# TeensySensor.net
KiCad netlist of a schematic drawn in EasyEDA Pro
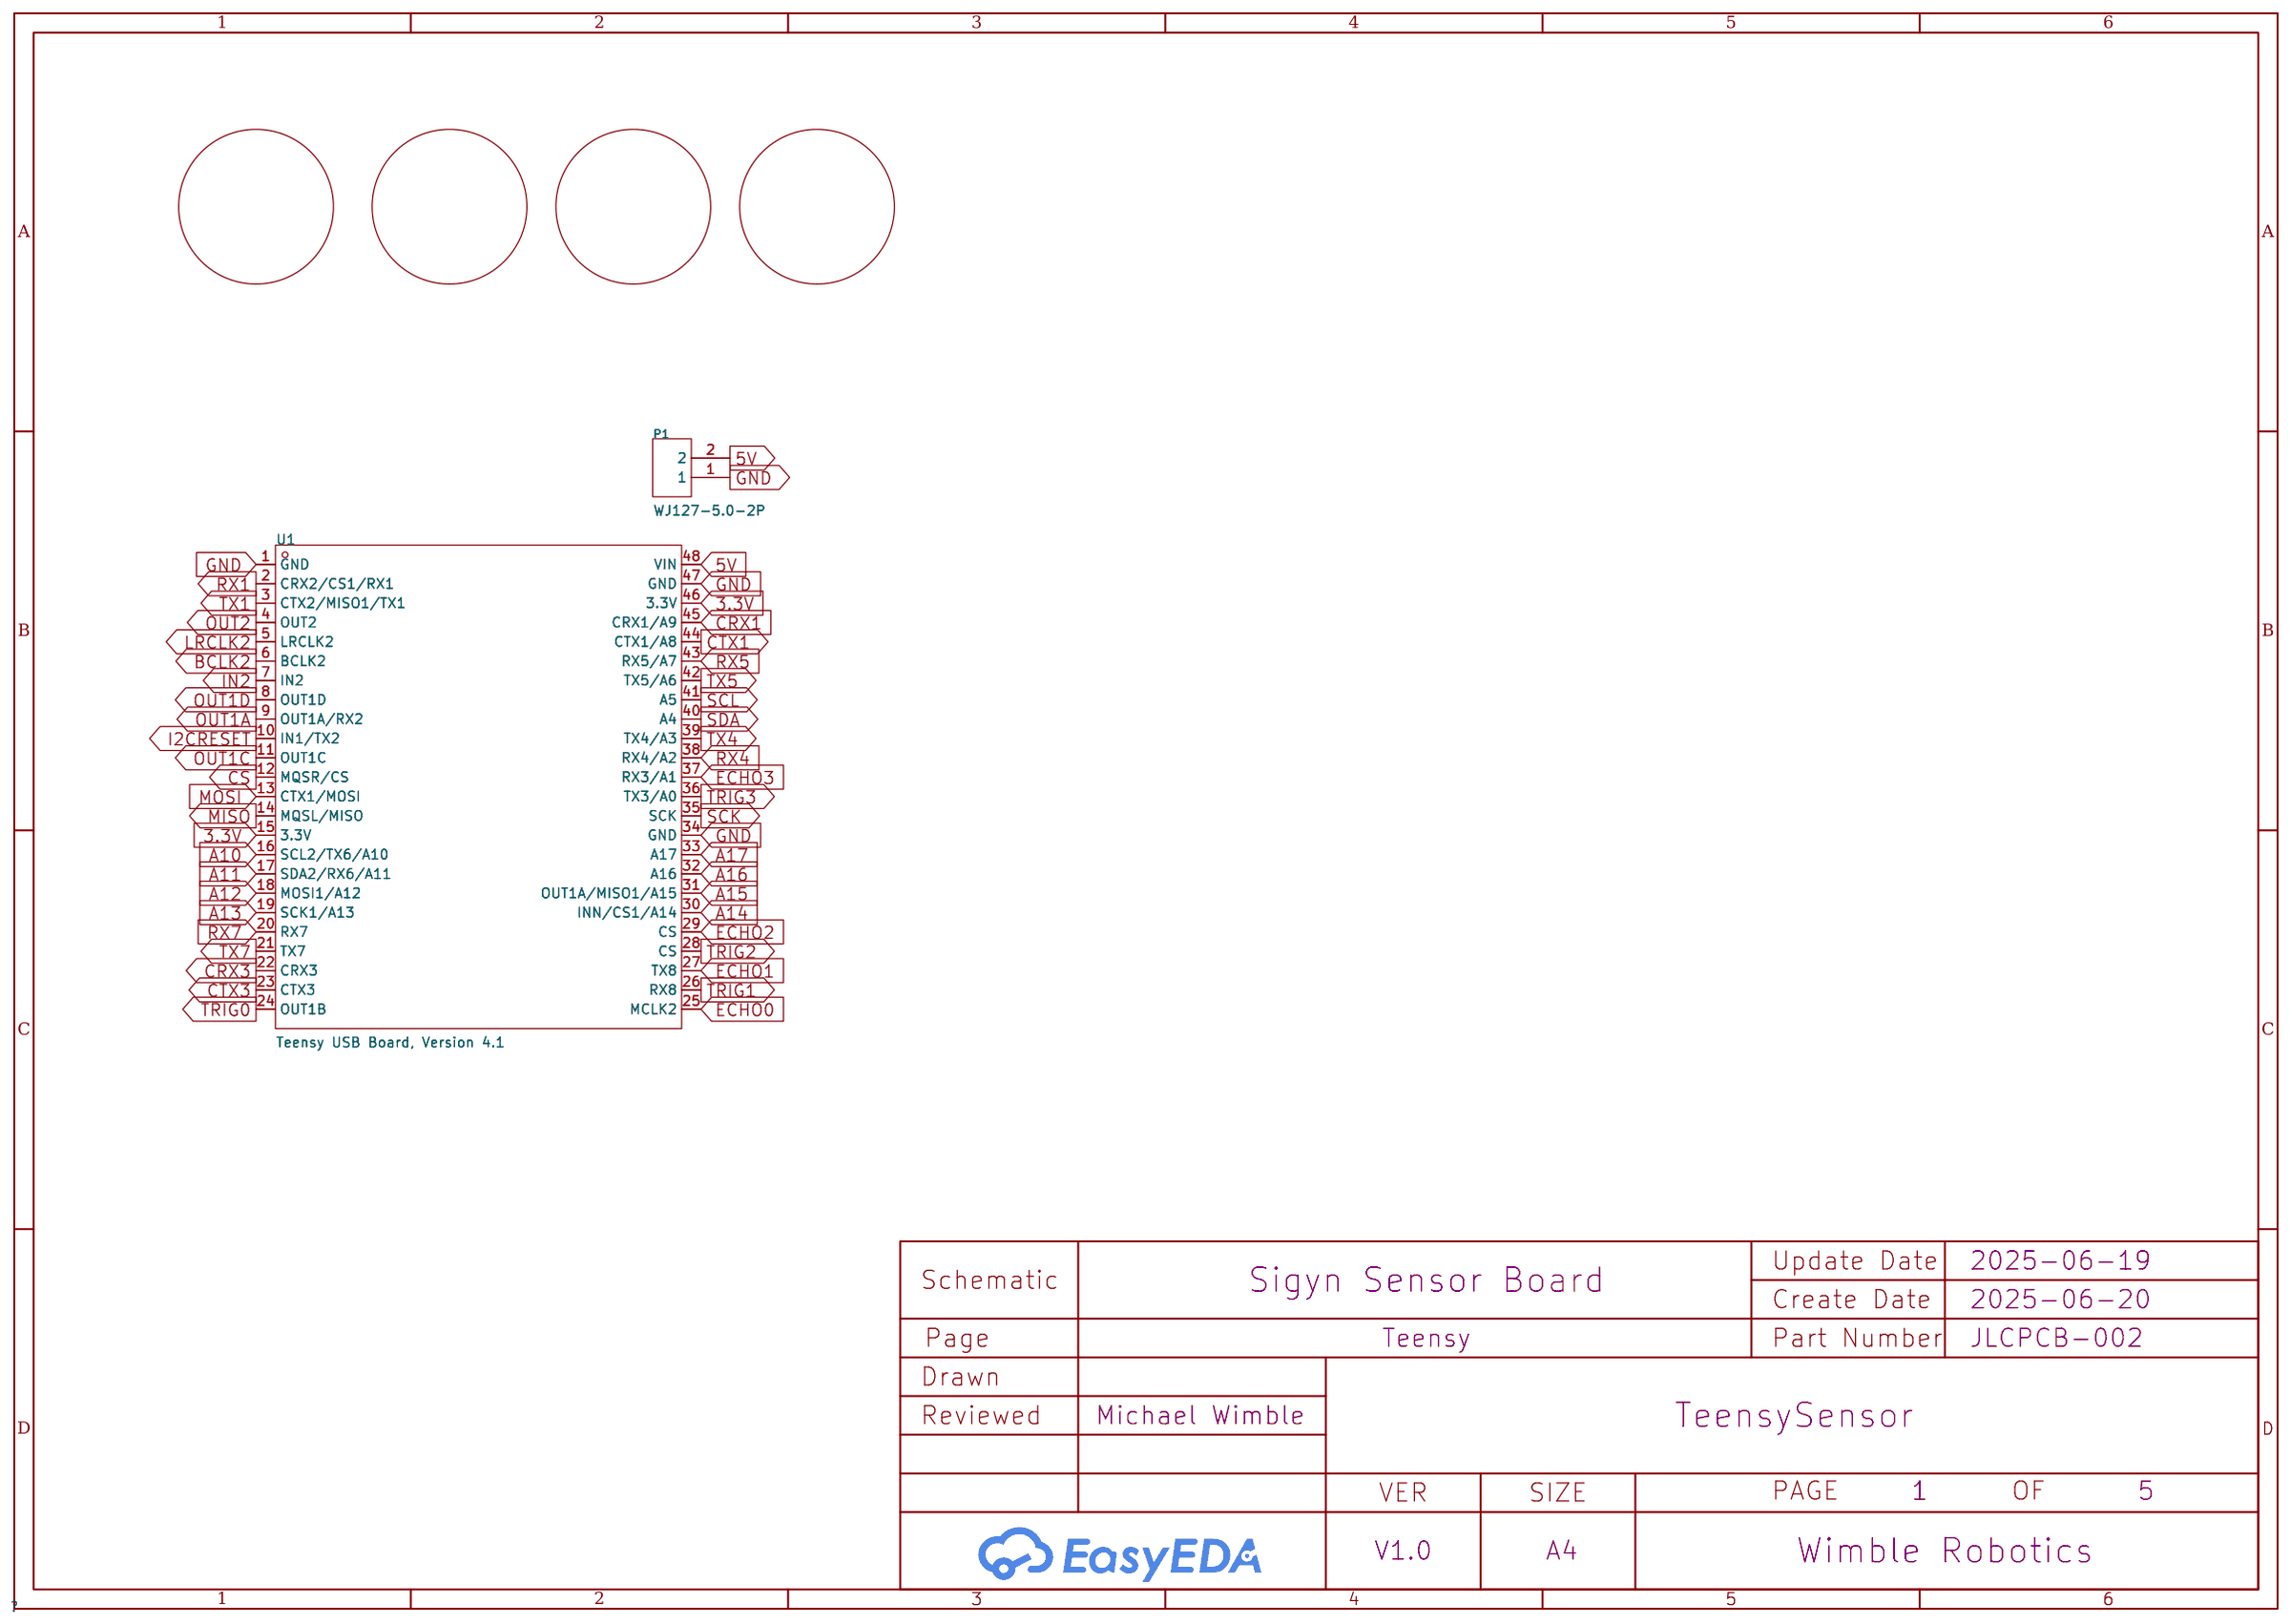
[diagram p0: Teensy]
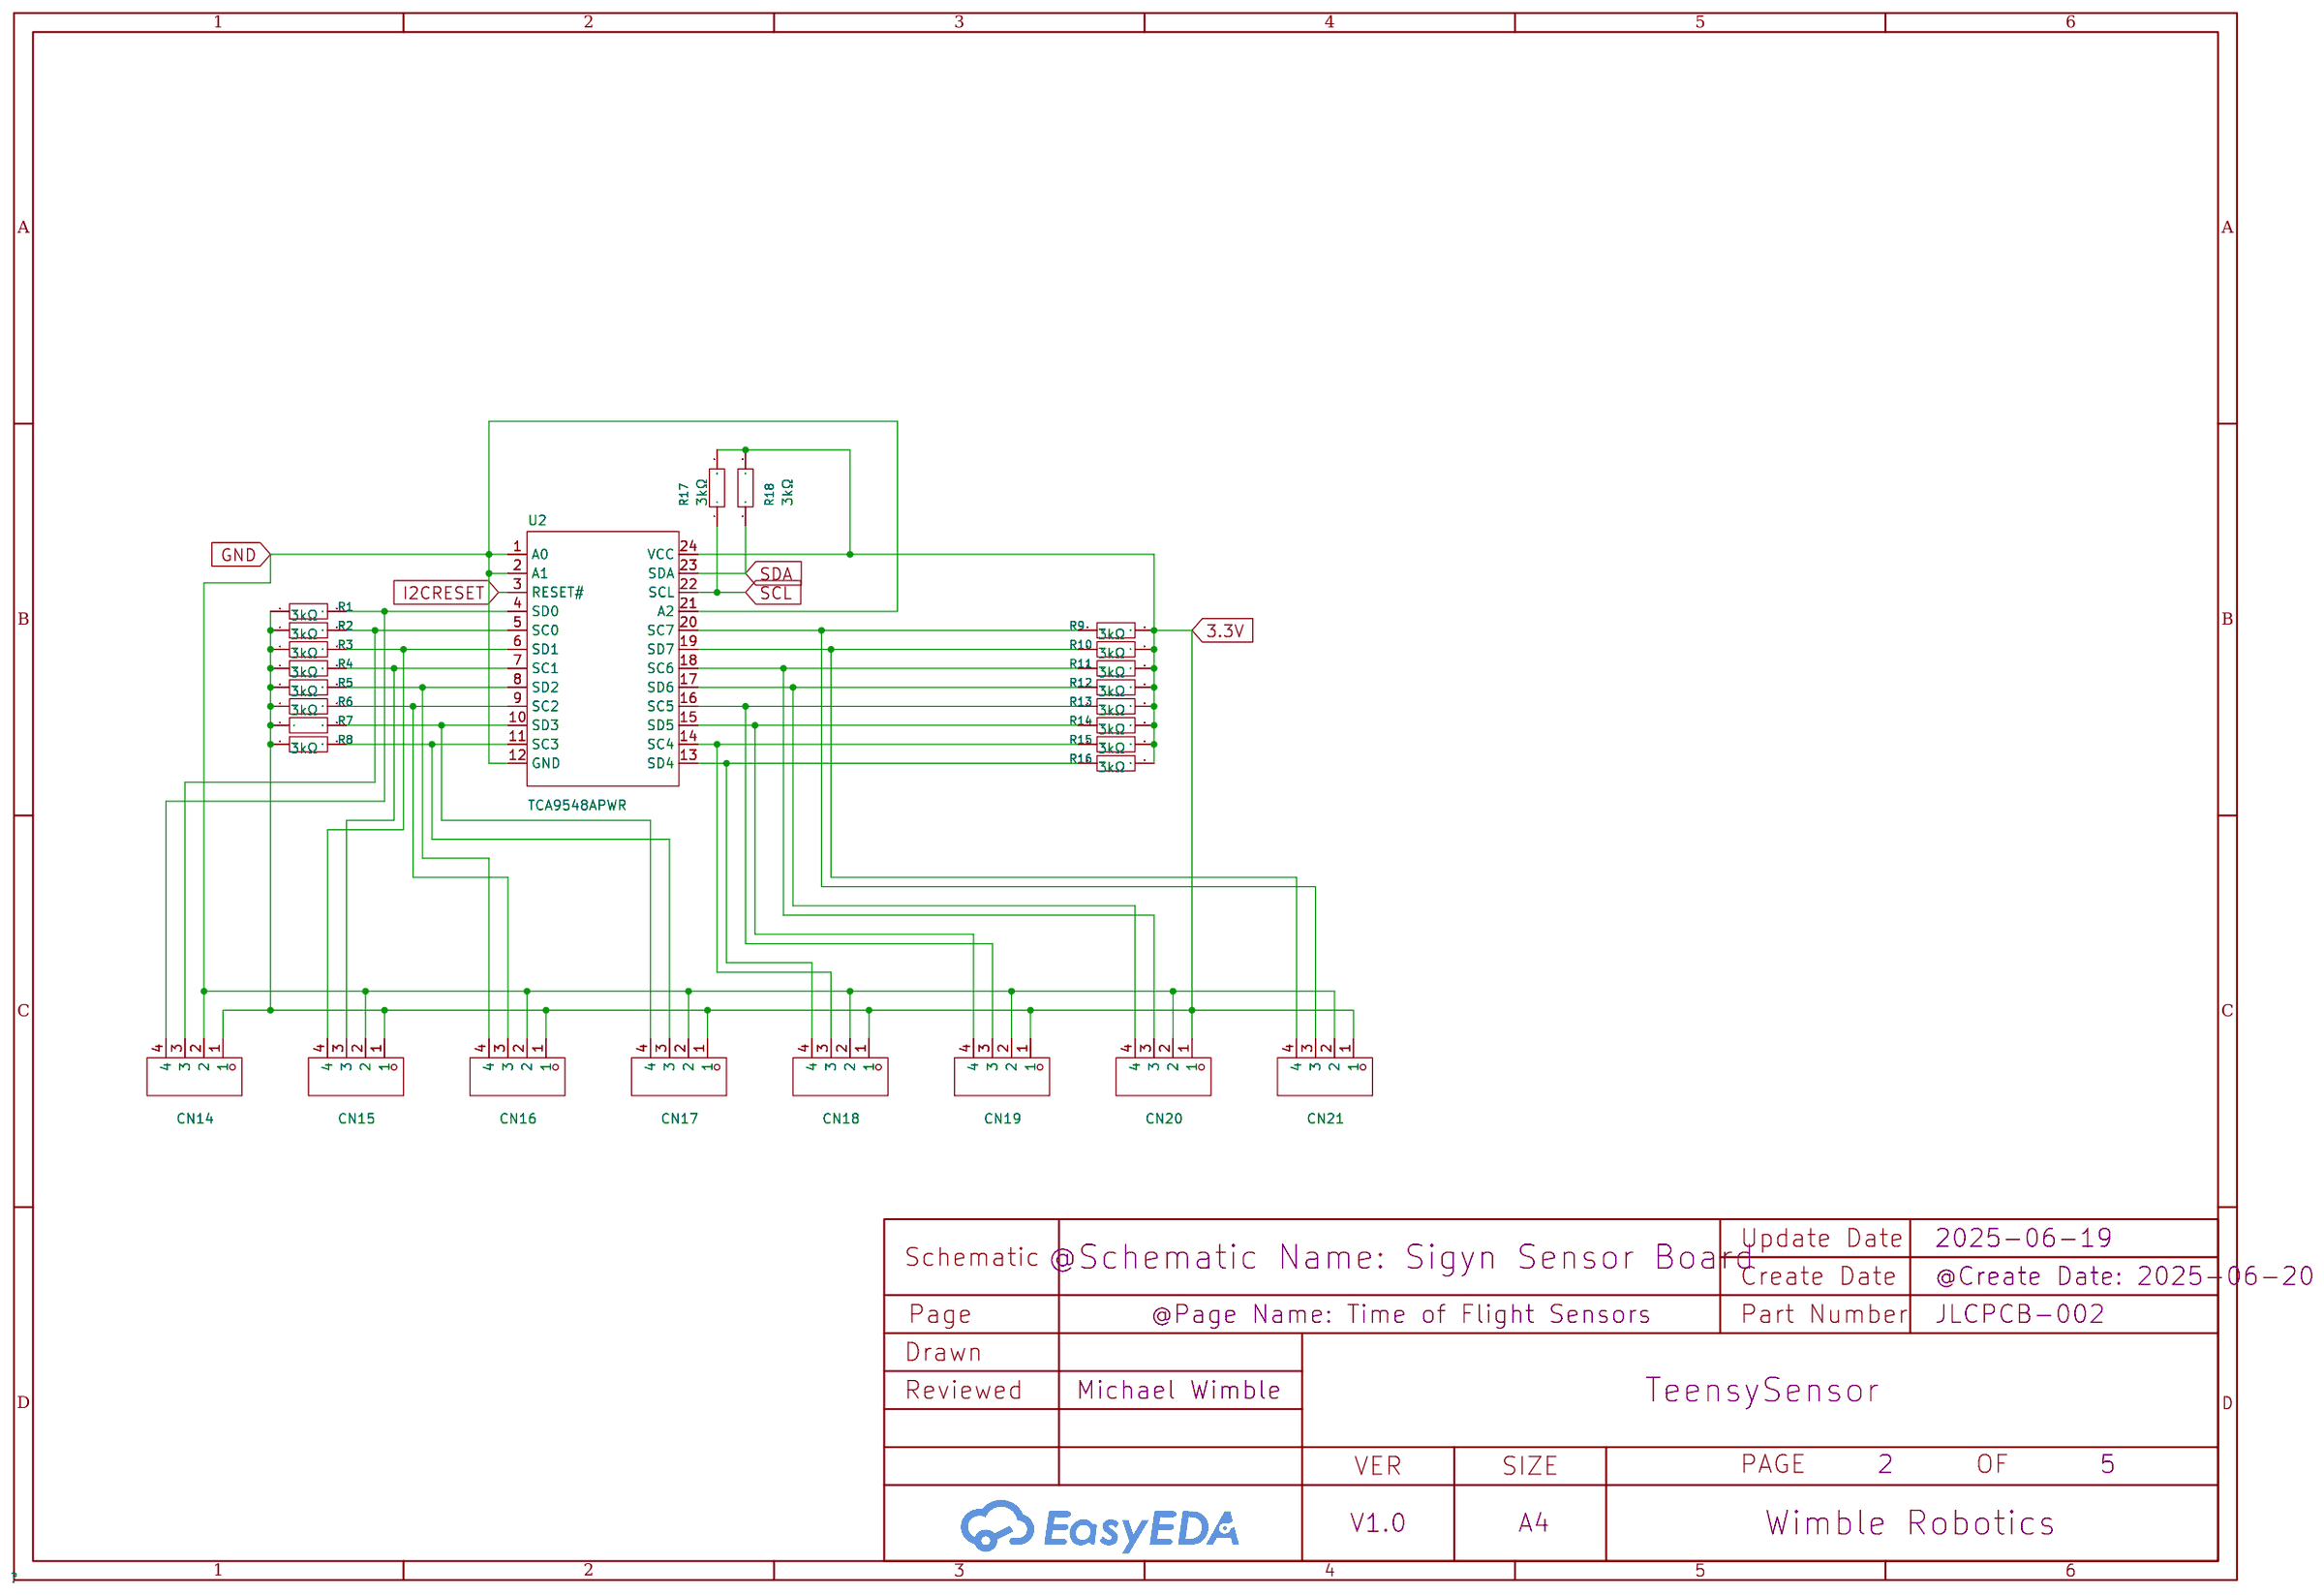
[diagram p1: Time of Flight Sensors]
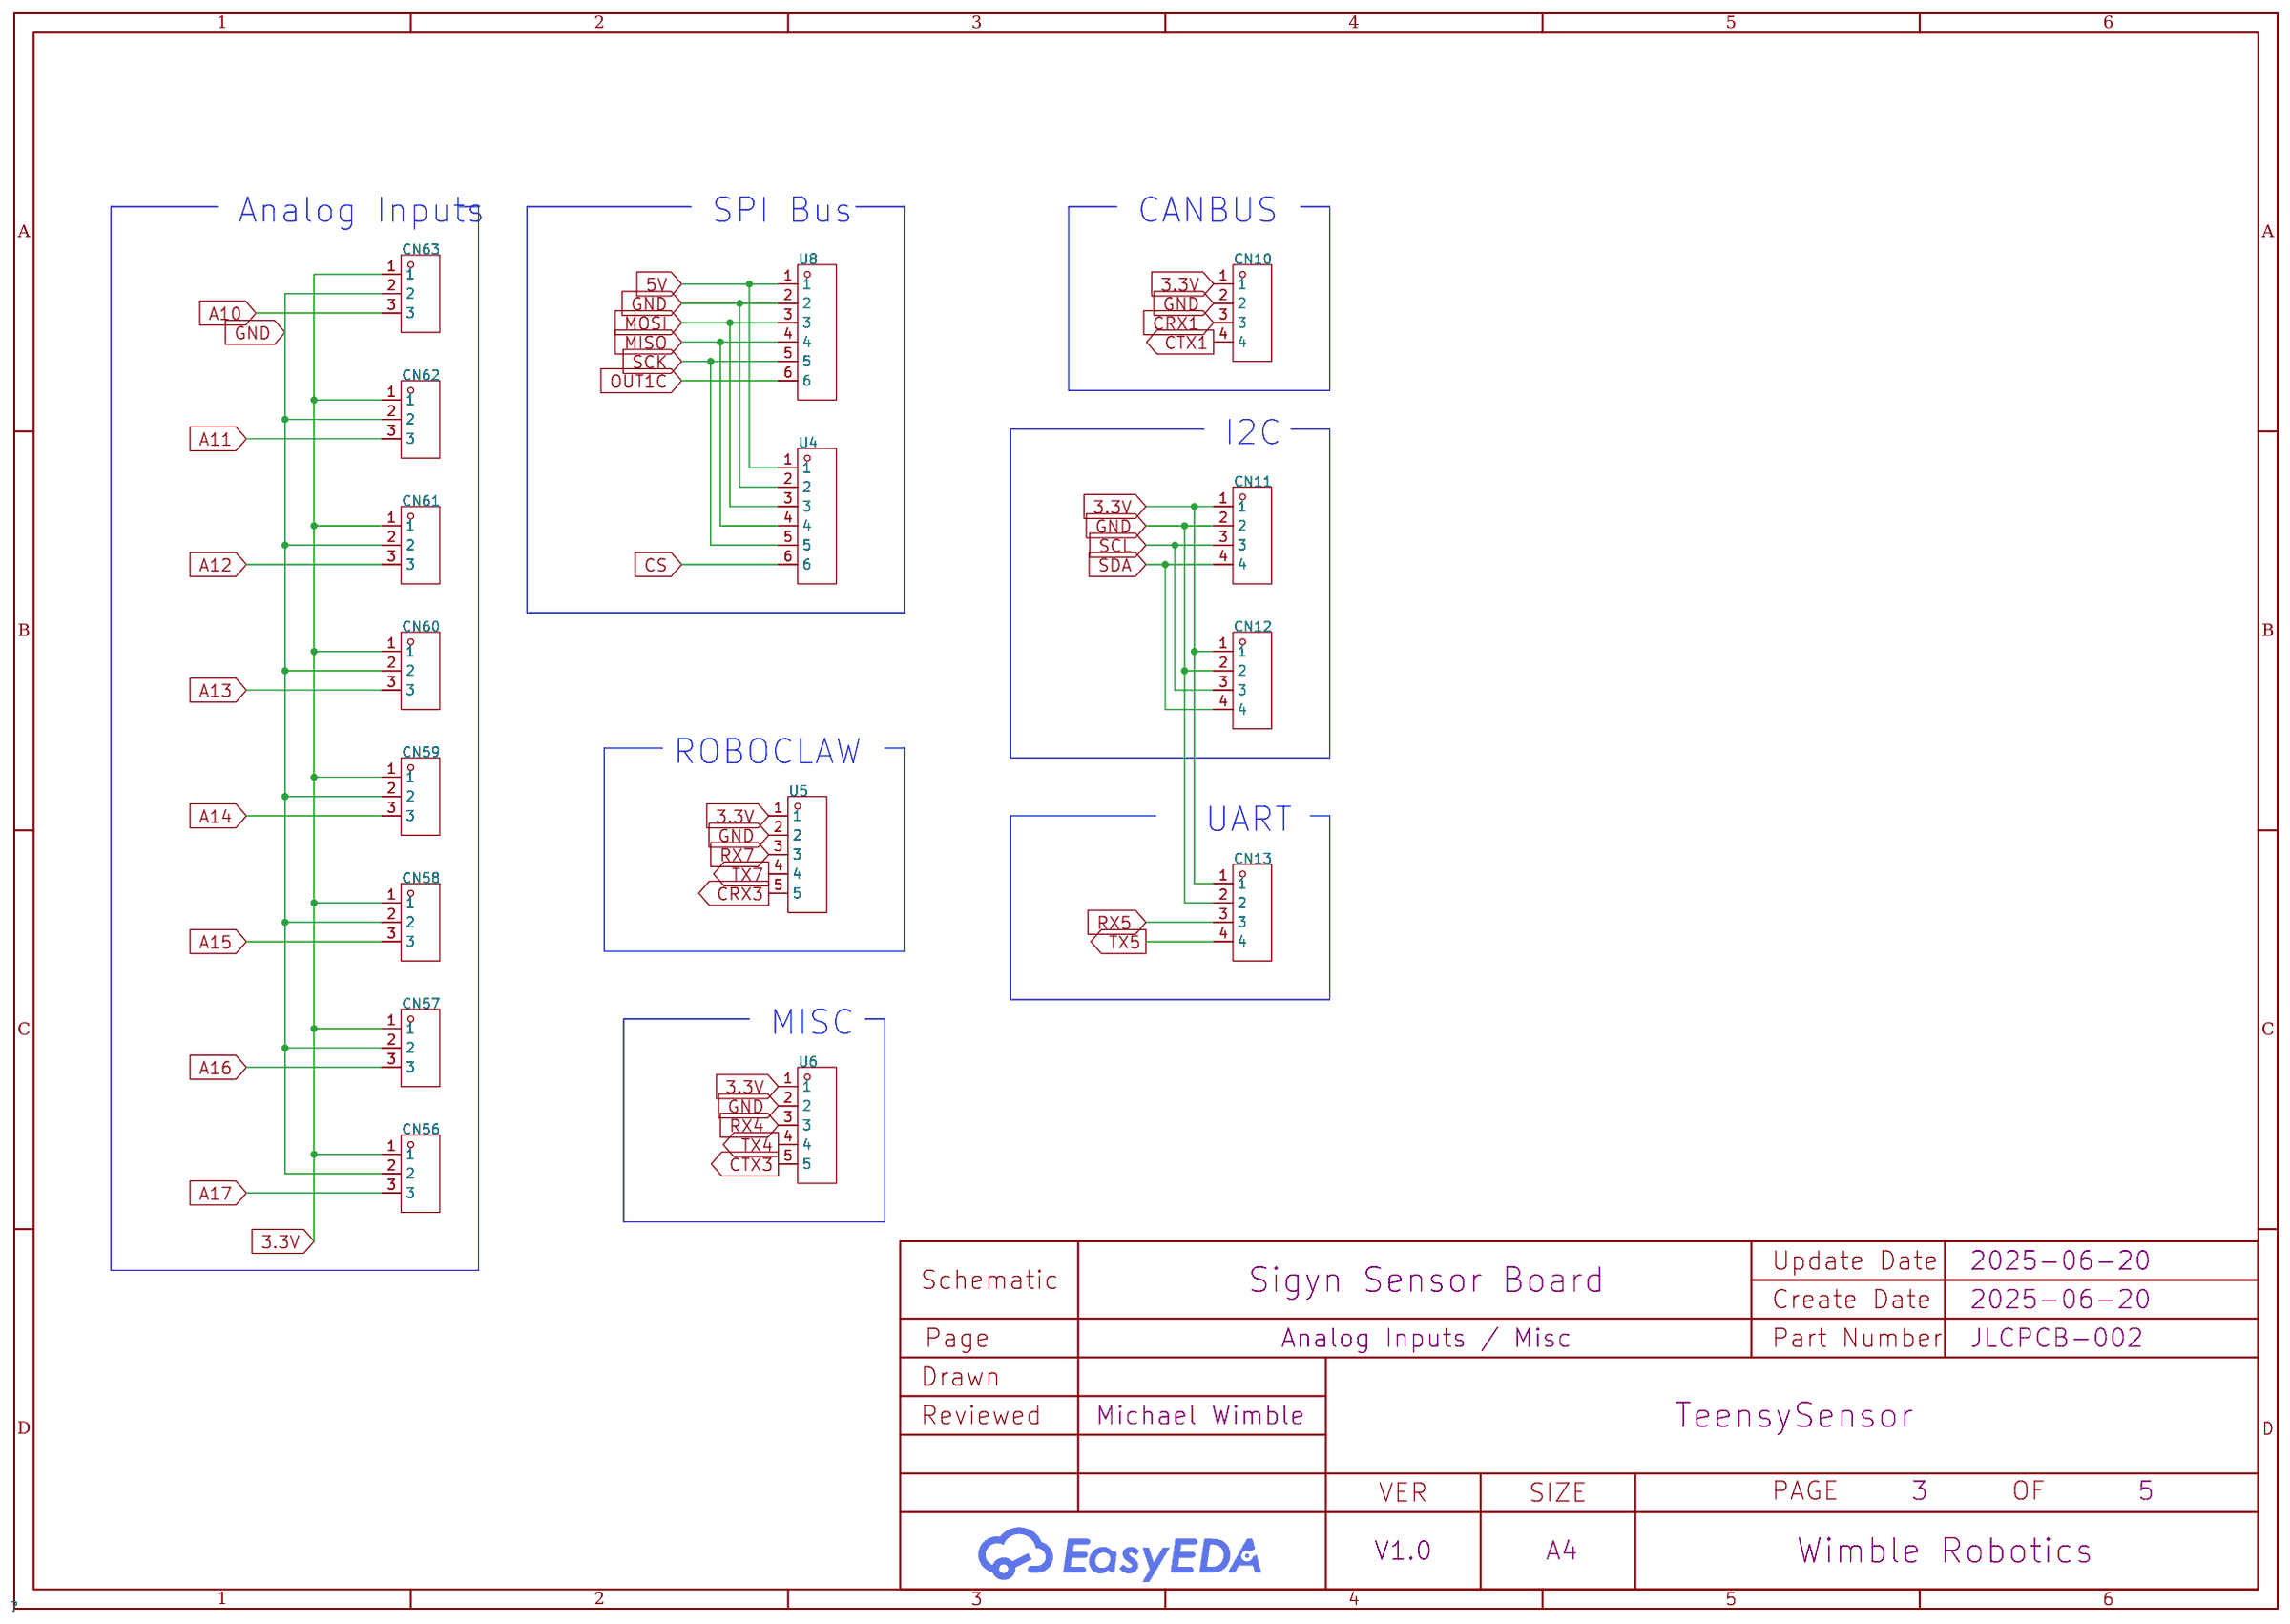
[diagram p2: Analog Inputs / Misc]
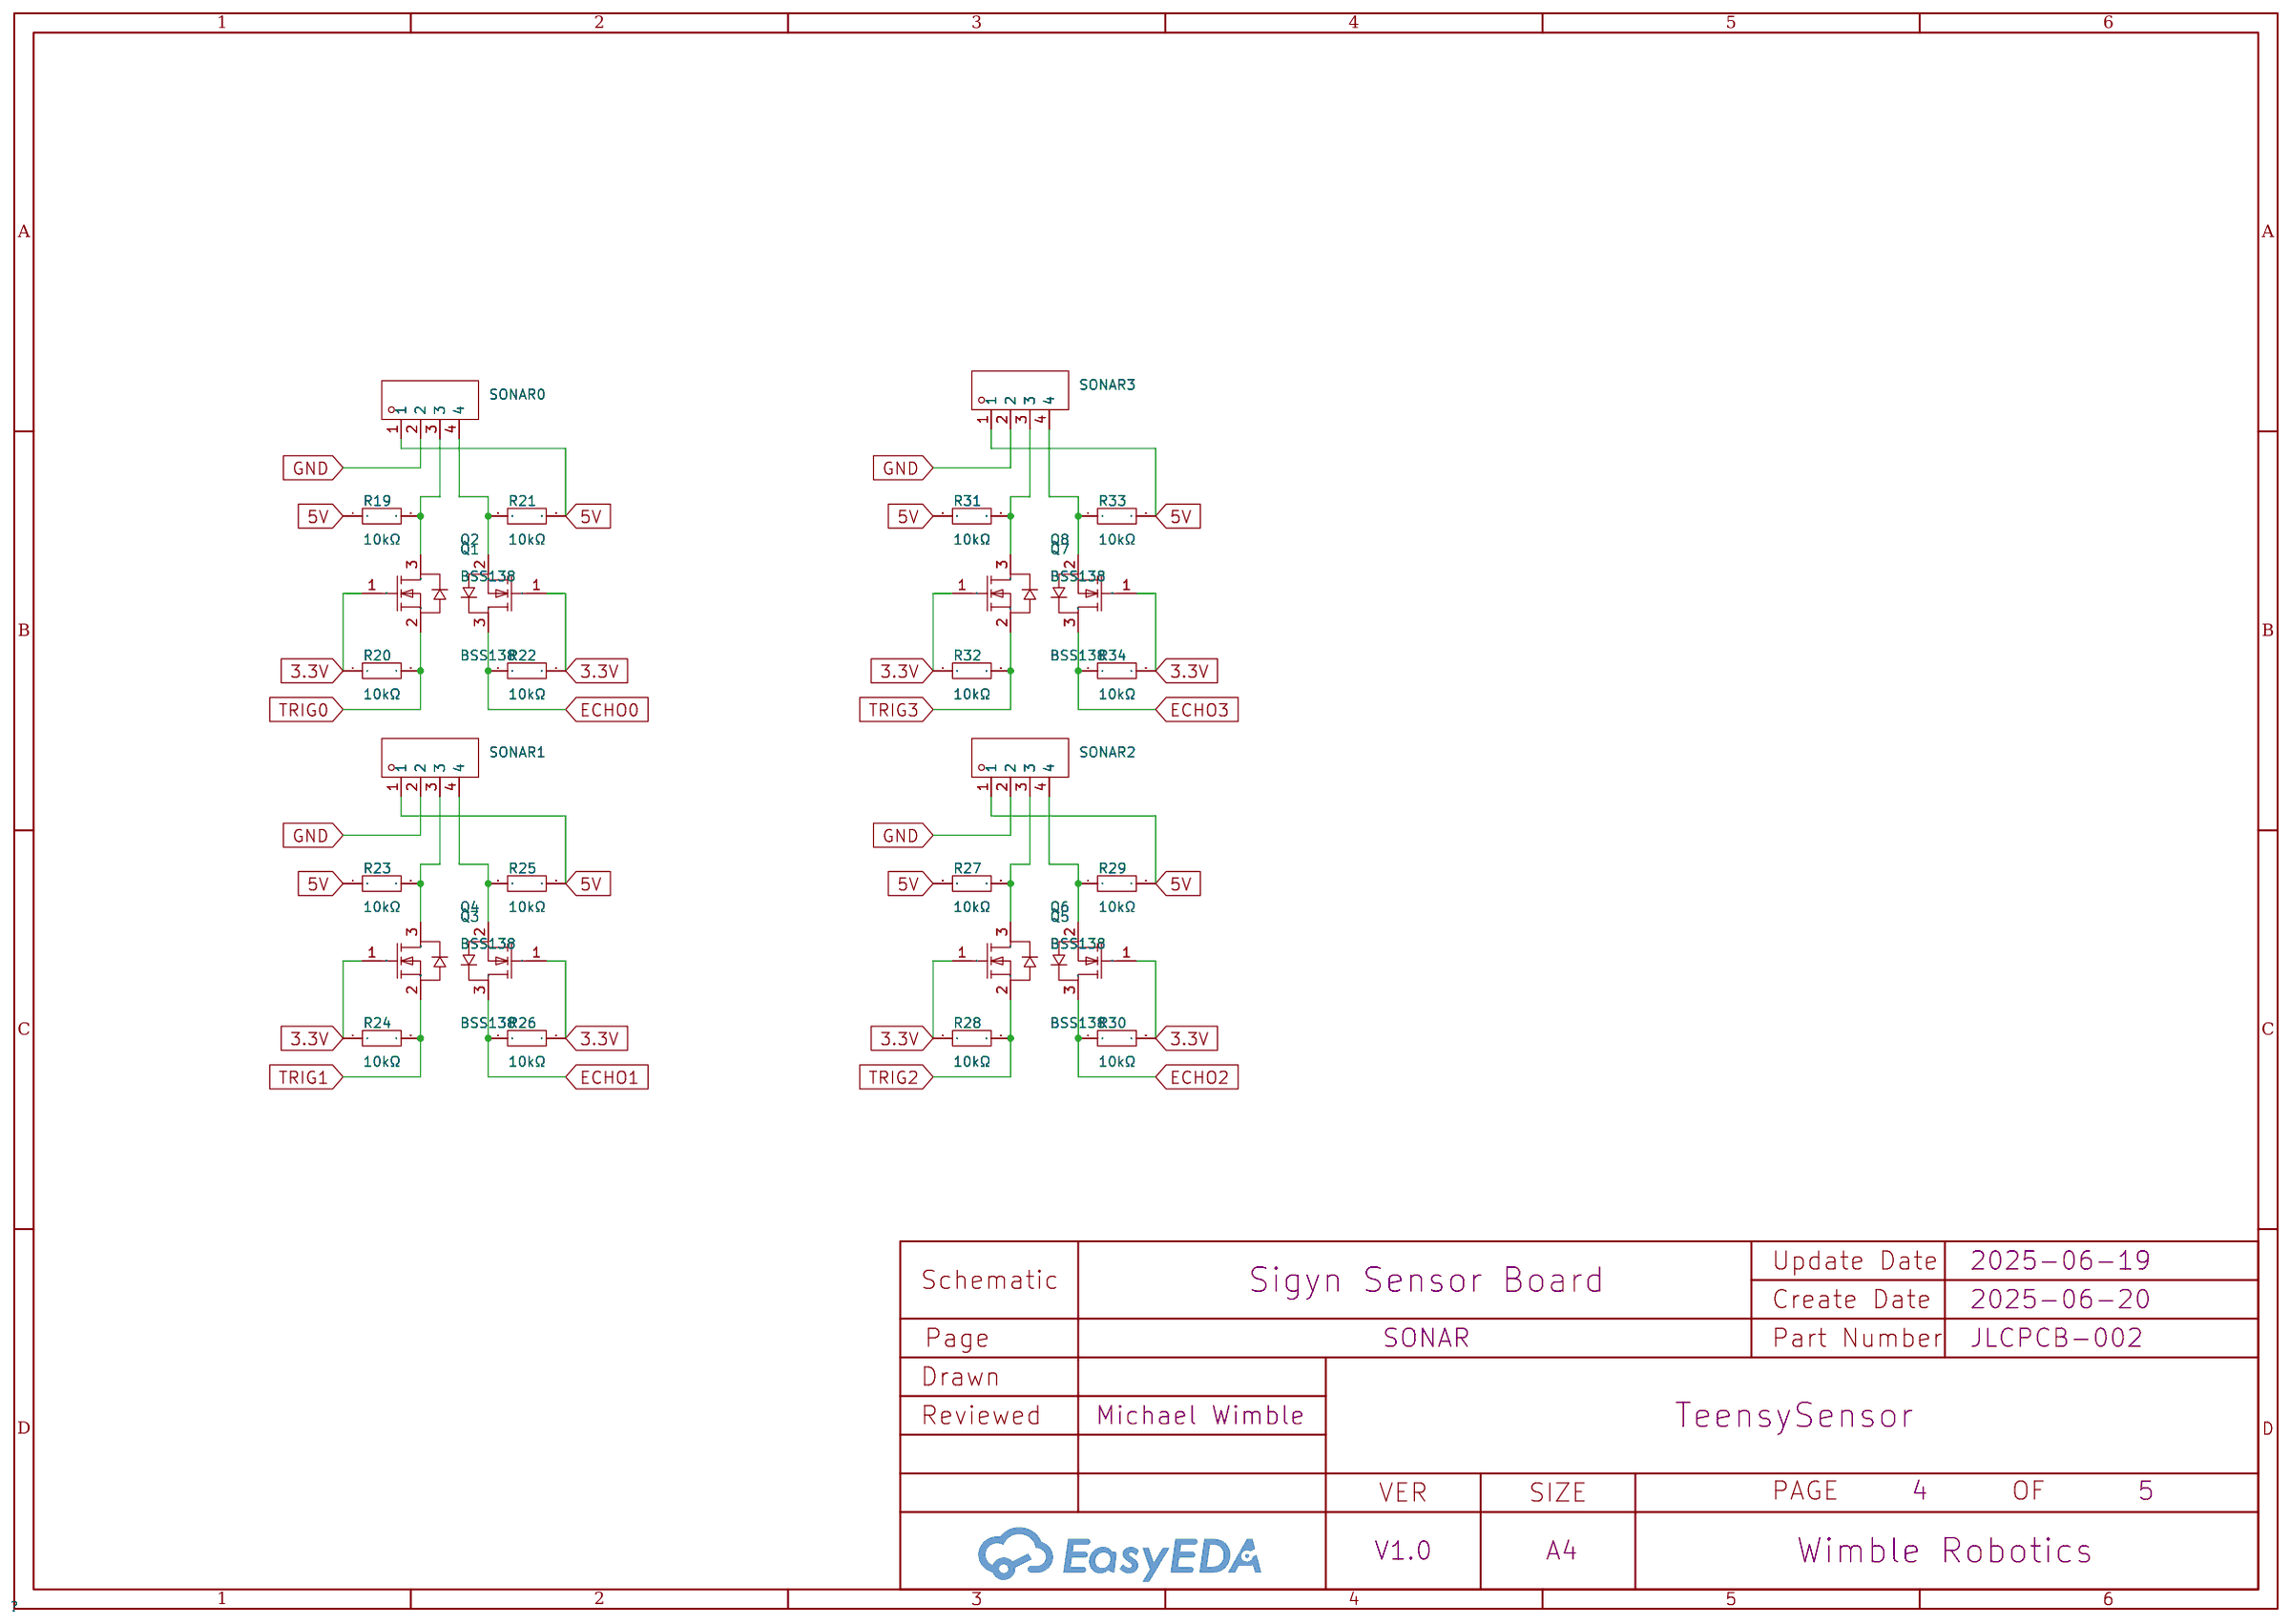
[diagram p3: SONAR]
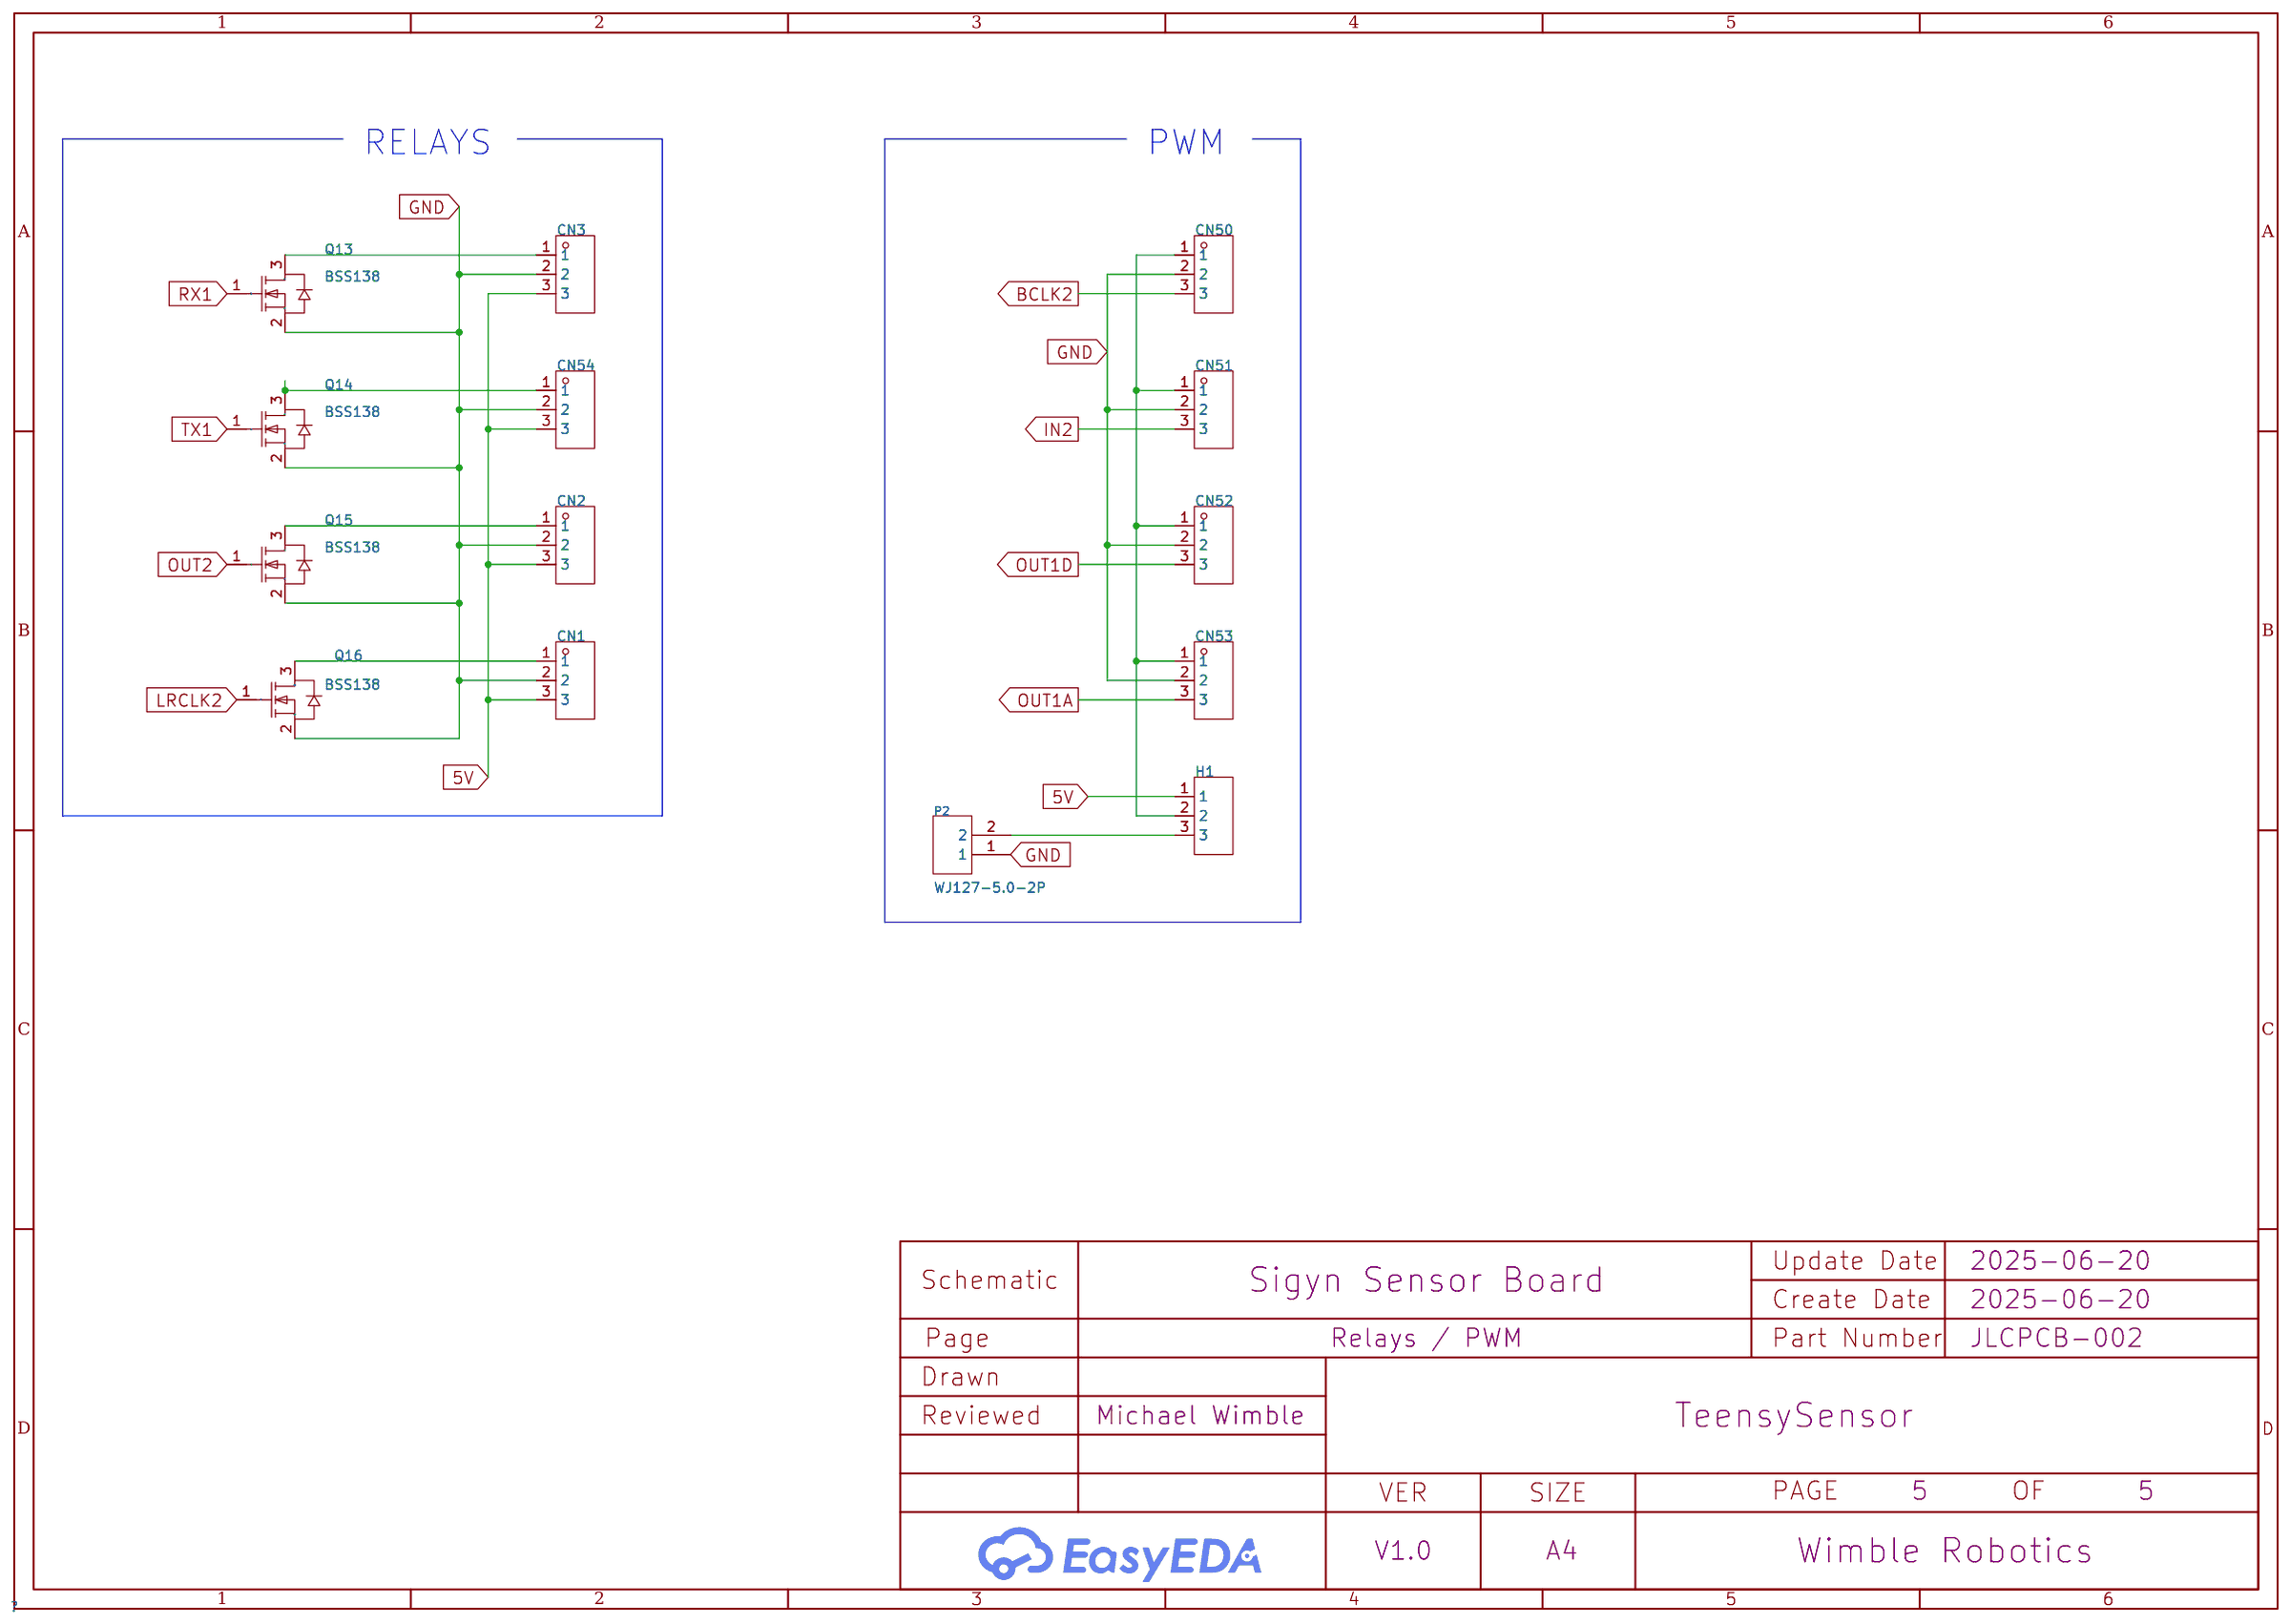
[diagram p4: Relays / PWM]

(export (version "E")
  (design (tool "Eeschema 10.0.6"))
  (components
    (comp (ref "P1")
      (value "WJ127-5.0-2P")
      (footprint "easyedapro:CONN-TH_2P-P5.00_CPC3703CTR")
      (fields (field (name "Manufacturer") "KANGNEX(康奈克斯电气)"))
      (libsource (lib "easyedapro") (part "WJ127-5.0-2P"))
    )
    (comp (ref "U1")
      (value "Teensy USB Board, Version 4.1")
      (footprint "easyedapro:COMM-TH_L61.0-W17.8-P2.54")
      (libsource (lib "easyedapro") (part "TEENSY USB BOARD, VERSION 4.1"))
    )
    (comp (ref "U12")
      (value "~")
      (footprint "easyedapro:3.5mm_Hole")
      (description "Mounting hole")
      (libsource (lib "easyedapro") (part "3.5MMHole"))
    )
    (comp (ref "U13")
      (value "~")
      (footprint "easyedapro:3.5mm_Hole")
      (description "Mounting hole")
      (libsource (lib "easyedapro") (part "3.5MMHole"))
    )
    (comp (ref "U14")
      (value "~")
      (footprint "easyedapro:3.5mm_Hole")
      (description "Mounting hole")
      (libsource (lib "easyedapro") (part "3.5MMHole"))
    )
    (comp (ref "U15")
      (value "~")
      (footprint "easyedapro:3.5mm_Hole")
      (description "Mounting hole")
      (libsource (lib "easyedapro") (part "3.5MMHole"))
    )
    (comp (ref "CN14")
      (value "ZX-XH2.54-4PZZ")
      (footprint "easyedapro:CONN-TH_4P-P2.50_4PIN")
      (fields (field (name "Manufacturer") "Megastar(兆星)"))
      (libsource (lib "easyedapro") (part "ZX-XH2.54-4PZZ"))
    )
    (comp (ref "CN15")
      (value "ZX-XH2.54-4PZZ")
      (footprint "easyedapro:CONN-TH_4P-P2.50_4PIN")
      (fields (field (name "Manufacturer") "Megastar(兆星)"))
      (libsource (lib "easyedapro") (part "ZX-XH2.54-4PZZ"))
    )
    (comp (ref "CN16")
      (value "ZX-XH2.54-4PZZ")
      (footprint "easyedapro:CONN-TH_4P-P2.50_4PIN")
      (fields (field (name "Manufacturer") "Megastar(兆星)"))
      (libsource (lib "easyedapro") (part "ZX-XH2.54-4PZZ"))
    )
    (comp (ref "CN17")
      (value "ZX-XH2.54-4PZZ")
      (footprint "easyedapro:CONN-TH_4P-P2.50_4PIN")
      (fields (field (name "Manufacturer") "Megastar(兆星)"))
      (libsource (lib "easyedapro") (part "ZX-XH2.54-4PZZ"))
    )
    (comp (ref "CN18")
      (value "ZX-XH2.54-4PZZ")
      (footprint "easyedapro:CONN-TH_4P-P2.50_4PIN")
      (fields (field (name "Manufacturer") "Megastar(兆星)"))
      (libsource (lib "easyedapro") (part "ZX-XH2.54-4PZZ"))
    )
    (comp (ref "CN19")
      (value "ZX-XH2.54-4PZZ")
      (footprint "easyedapro:CONN-TH_4P-P2.50_4PIN")
      (fields (field (name "Manufacturer") "Megastar(兆星)"))
      (libsource (lib "easyedapro") (part "ZX-XH2.54-4PZZ"))
    )
    (comp (ref "CN20")
      (value "ZX-XH2.54-4PZZ")
      (footprint "easyedapro:CONN-TH_4P-P2.50_4PIN")
      (fields (field (name "Manufacturer") "Megastar(兆星)"))
      (libsource (lib "easyedapro") (part "ZX-XH2.54-4PZZ"))
    )
    (comp (ref "CN21")
      (value "ZX-XH2.54-4PZZ")
      (footprint "easyedapro:CONN-TH_4P-P2.50_4PIN")
      (fields (field (name "Manufacturer") "Megastar(兆星)"))
      (libsource (lib "easyedapro") (part "ZX-XH2.54-4PZZ"))
    )
    (comp (ref "R1")
      (value "3kΩ")
      (footprint "easyedapro:R0603")
      (fields
        (field (name "Manufacturer Part") "0603WAF3001T5E")
        (field (name "Manufacturer") "UNI-ROYAL(厚声)")
      )
      (libsource (lib "easyedapro") (part "0603WAF3001T5E"))
    )
    (comp (ref "R2")
      (value "3kΩ")
      (footprint "easyedapro:R0603")
      (fields
        (field (name "Manufacturer Part") "0603WAF3001T5E")
        (field (name "Manufacturer") "UNI-ROYAL(厚声)")
      )
      (libsource (lib "easyedapro") (part "0603WAF3001T5E"))
    )
    (comp (ref "R3")
      (value "3kΩ")
      (footprint "easyedapro:R0603")
      (fields
        (field (name "Manufacturer Part") "0603WAF3001T5E")
        (field (name "Manufacturer") "UNI-ROYAL(厚声)")
      )
      (libsource (lib "easyedapro") (part "0603WAF3001T5E"))
    )
    (comp (ref "R4")
      (value "3kΩ")
      (footprint "easyedapro:R0603")
      (fields
        (field (name "Manufacturer Part") "0603WAF3001T5E")
        (field (name "Manufacturer") "UNI-ROYAL(厚声)")
      )
      (libsource (lib "easyedapro") (part "0603WAF3001T5E"))
    )
    (comp (ref "R5")
      (value "3kΩ")
      (footprint "easyedapro:R0603")
      (fields
        (field (name "Manufacturer Part") "0603WAF3001T5E")
        (field (name "Manufacturer") "UNI-ROYAL(厚声)")
      )
      (libsource (lib "easyedapro") (part "0603WAF3001T5E"))
    )
    (comp (ref "R6")
      (value "3kΩ")
      (footprint "easyedapro:R0603")
      (fields
        (field (name "Manufacturer Part") "0603WAF3001T5E")
        (field (name "Manufacturer") "UNI-ROYAL(厚声)")
      )
      (libsource (lib "easyedapro") (part "0603WAF3001T5E"))
    )
    (comp (ref "R7")
      (value "3kΩ")
      (footprint "easyedapro:R0603")
      (fields
        (field (name "Manufacturer Part") "0603WAF3001T5E")
        (field (name "Manufacturer") "UNI-ROYAL(厚声)")
      )
      (libsource (lib "easyedapro") (part "0603WAF3001T5E"))
    )
    (comp (ref "R8")
      (value "3kΩ")
      (footprint "easyedapro:R0603")
      (fields
        (field (name "Manufacturer Part") "0603WAF3001T5E")
        (field (name "Manufacturer") "UNI-ROYAL(厚声)")
      )
      (libsource (lib "easyedapro") (part "0603WAF3001T5E"))
    )
    (comp (ref "R9")
      (value "3kΩ")
      (footprint "easyedapro:R0603")
      (fields
        (field (name "Manufacturer Part") "0603WAF3001T5E")
        (field (name "Manufacturer") "UNI-ROYAL(厚声)")
      )
      (libsource (lib "easyedapro") (part "0603WAF3001T5E"))
    )
    (comp (ref "R10")
      (value "3kΩ")
      (footprint "easyedapro:R0603")
      (fields
        (field (name "Manufacturer Part") "0603WAF3001T5E")
        (field (name "Manufacturer") "UNI-ROYAL(厚声)")
      )
      (libsource (lib "easyedapro") (part "0603WAF3001T5E"))
    )
    (comp (ref "R11")
      (value "3kΩ")
      (footprint "easyedapro:R0603")
      (fields
        (field (name "Manufacturer Part") "0603WAF3001T5E")
        (field (name "Manufacturer") "UNI-ROYAL(厚声)")
      )
      (libsource (lib "easyedapro") (part "0603WAF3001T5E"))
    )
    (comp (ref "R12")
      (value "3kΩ")
      (footprint "easyedapro:R0603")
      (fields
        (field (name "Manufacturer Part") "0603WAF3001T5E")
        (field (name "Manufacturer") "UNI-ROYAL(厚声)")
      )
      (libsource (lib "easyedapro") (part "0603WAF3001T5E"))
    )
    (comp (ref "R13")
      (value "3kΩ")
      (footprint "easyedapro:R0603")
      (fields
        (field (name "Manufacturer Part") "0603WAF3001T5E")
        (field (name "Manufacturer") "UNI-ROYAL(厚声)")
      )
      (libsource (lib "easyedapro") (part "0603WAF3001T5E"))
    )
    (comp (ref "R14")
      (value "3kΩ")
      (footprint "easyedapro:R0603")
      (fields
        (field (name "Manufacturer Part") "0603WAF3001T5E")
        (field (name "Manufacturer") "UNI-ROYAL(厚声)")
      )
      (libsource (lib "easyedapro") (part "0603WAF3001T5E"))
    )
    (comp (ref "R15")
      (value "3kΩ")
      (footprint "easyedapro:R0603")
      (fields
        (field (name "Manufacturer Part") "0603WAF3001T5E")
        (field (name "Manufacturer") "UNI-ROYAL(厚声)")
      )
      (libsource (lib "easyedapro") (part "0603WAF3001T5E"))
    )
    (comp (ref "R16")
      (value "3kΩ")
      (footprint "easyedapro:R0603")
      (fields
        (field (name "Manufacturer Part") "0603WAF3001T5E")
        (field (name "Manufacturer") "UNI-ROYAL(厚声)")
      )
      (libsource (lib "easyedapro") (part "0603WAF3001T5E"))
    )
    (comp (ref "R17")
      (value "3kΩ")
      (footprint "easyedapro:R0603")
      (fields
        (field (name "Manufacturer Part") "0603WAF3001T5E")
        (field (name "Manufacturer") "UNI-ROYAL(厚声)")
      )
      (libsource (lib "easyedapro") (part "0603WAF3001T5E"))
    )
    (comp (ref "R18")
      (value "3kΩ")
      (footprint "easyedapro:R0603")
      (fields
        (field (name "Manufacturer Part") "0603WAF3001T5E")
        (field (name "Manufacturer") "UNI-ROYAL(厚声)")
      )
      (libsource (lib "easyedapro") (part "0603WAF3001T5E"))
    )
    (comp (ref "U2")
      (value "TCA9548APWR")
      (footprint "easyedapro:TSSOP-24_L7.8-W4.4-P0.65-LS6.4-BL")
      (fields (field (name "Manufacturer") "TI(德州仪器)"))
      (libsource (lib "easyedapro") (part "TCA9548APWR"))
    )
    (comp (ref "CN10")
      (value "ZX-XH2.54-4PZZ")
      (footprint "easyedapro:CONN-TH_4P-P2.50_4PIN")
      (fields (field (name "Manufacturer") "Megastar(兆星)"))
      (libsource (lib "easyedapro") (part "ZX-XH2.54-4PZZ"))
    )
    (comp (ref "CN11")
      (value "ZX-XH2.54-4PZZ")
      (footprint "easyedapro:CONN-TH_4P-P2.50_4PIN")
      (fields (field (name "Manufacturer") "Megastar(兆星)"))
      (libsource (lib "easyedapro") (part "ZX-XH2.54-4PZZ"))
    )
    (comp (ref "CN12")
      (value "ZX-XH2.54-4PZZ")
      (footprint "easyedapro:CONN-TH_4P-P2.50_4PIN")
      (fields (field (name "Manufacturer") "Megastar(兆星)"))
      (libsource (lib "easyedapro") (part "ZX-XH2.54-4PZZ"))
    )
    (comp (ref "CN13")
      (value "ZX-XH2.54-4PZZ")
      (footprint "easyedapro:CONN-TH_4P-P2.50_4PIN")
      (fields (field (name "Manufacturer") "Megastar(兆星)"))
      (libsource (lib "easyedapro") (part "ZX-XH2.54-4PZZ"))
    )
    (comp (ref "CN56")
      (value "ZX-XH2.54-3PZZ")
      (footprint "easyedapro:CONN-TH_3P-P2.54_2501S-3P")
      (fields (field (name "Manufacturer") "Megastar(兆星)"))
      (libsource (lib "easyedapro") (part "ZX-XH2.54-3PZZ"))
    )
    (comp (ref "CN57")
      (value "ZX-XH2.54-3PZZ")
      (footprint "easyedapro:CONN-TH_3P-P2.54_2501S-3P")
      (fields (field (name "Manufacturer") "Megastar(兆星)"))
      (libsource (lib "easyedapro") (part "ZX-XH2.54-3PZZ"))
    )
    (comp (ref "CN58")
      (value "ZX-XH2.54-3PZZ")
      (footprint "easyedapro:CONN-TH_3P-P2.54_2501S-3P")
      (fields (field (name "Manufacturer") "Megastar(兆星)"))
      (libsource (lib "easyedapro") (part "ZX-XH2.54-3PZZ"))
    )
    (comp (ref "CN59")
      (value "ZX-XH2.54-3PZZ")
      (footprint "easyedapro:CONN-TH_3P-P2.54_2501S-3P")
      (fields (field (name "Manufacturer") "Megastar(兆星)"))
      (libsource (lib "easyedapro") (part "ZX-XH2.54-3PZZ"))
    )
    (comp (ref "CN60")
      (value "ZX-XH2.54-3PZZ")
      (footprint "easyedapro:CONN-TH_3P-P2.54_2501S-3P")
      (fields (field (name "Manufacturer") "Megastar(兆星)"))
      (libsource (lib "easyedapro") (part "ZX-XH2.54-3PZZ"))
    )
    (comp (ref "CN61")
      (value "ZX-XH2.54-3PZZ")
      (footprint "easyedapro:CONN-TH_3P-P2.54_2501S-3P")
      (fields (field (name "Manufacturer") "Megastar(兆星)"))
      (libsource (lib "easyedapro") (part "ZX-XH2.54-3PZZ"))
    )
    (comp (ref "CN62")
      (value "ZX-XH2.54-3PZZ")
      (footprint "easyedapro:CONN-TH_3P-P2.54_2501S-3P")
      (fields (field (name "Manufacturer") "Megastar(兆星)"))
      (libsource (lib "easyedapro") (part "ZX-XH2.54-3PZZ"))
    )
    (comp (ref "CN63")
      (value "ZX-XH2.54-3PZZ")
      (footprint "easyedapro:CONN-TH_3P-P2.54_2501S-3P")
      (fields (field (name "Manufacturer") "Megastar(兆星)"))
      (libsource (lib "easyedapro") (part "ZX-XH2.54-3PZZ"))
    )
    (comp (ref "U4")
      (value "ZX-XH2.54-6PZZ")
      (footprint "easyedapro:CONN-TH_6P-P2.50_ZX-XH2.54-6PZZ")
      (fields (field (name "Manufacturer") "Megastar(兆星)"))
      (libsource (lib "easyedapro") (part "ZX-XH2.54-6PZZ"))
    )
    (comp (ref "U5")
      (value "ZX-XH2.54-5PZZ")
      (footprint "easyedapro:CONN-TH_5P-P2.50_ZX-XH2.54-5PZZ")
      (fields (field (name "Manufacturer") "Megastar(兆星)"))
      (libsource (lib "easyedapro") (part "ZX-XH2.54-5PZZ"))
    )
    (comp (ref "U6")
      (value "ZX-XH2.54-5PZZ")
      (footprint "easyedapro:CONN-TH_5P-P2.50_ZX-XH2.54-5PZZ")
      (fields (field (name "Manufacturer") "Megastar(兆星)"))
      (libsource (lib "easyedapro") (part "ZX-XH2.54-5PZZ"))
    )
    (comp (ref "U8")
      (value "ZX-XH2.54-6PZZ")
      (footprint "easyedapro:CONN-TH_6P-P2.50_ZX-XH2.54-6PZZ")
      (fields (field (name "Manufacturer") "Megastar(兆星)"))
      (libsource (lib "easyedapro") (part "ZX-XH2.54-6PZZ"))
    )
    (comp (ref "Q1")
      (value "BSS138")
      (footprint "easyedapro:SOT-23-3_L2.9-W1.6-P1.90-LS2.8-BR")
      (fields (field (name "Manufacturer") "TECH PUBLIC(台舟)"))
      (libsource (lib "easyedapro") (part "BSS138_C18212695"))
    )
    (comp (ref "Q2")
      (value "BSS138")
      (footprint "easyedapro:SOT-23-3_L2.9-W1.6-P1.90-LS2.8-BR")
      (fields (field (name "Manufacturer") "TECH PUBLIC(台舟)"))
      (libsource (lib "easyedapro") (part "BSS138_C18212695"))
    )
    (comp (ref "Q3")
      (value "BSS138")
      (footprint "easyedapro:SOT-23-3_L2.9-W1.6-P1.90-LS2.8-BR")
      (fields (field (name "Manufacturer") "TECH PUBLIC(台舟)"))
      (libsource (lib "easyedapro") (part "BSS138_C18212695"))
    )
    (comp (ref "Q4")
      (value "BSS138")
      (footprint "easyedapro:SOT-23-3_L2.9-W1.6-P1.90-LS2.8-BR")
      (fields (field (name "Manufacturer") "TECH PUBLIC(台舟)"))
      (libsource (lib "easyedapro") (part "BSS138_C18212695"))
    )
    (comp (ref "Q5")
      (value "BSS138")
      (footprint "easyedapro:SOT-23-3_L2.9-W1.6-P1.90-LS2.8-BR")
      (fields (field (name "Manufacturer") "TECH PUBLIC(台舟)"))
      (libsource (lib "easyedapro") (part "BSS138_C18212695"))
    )
    (comp (ref "Q6")
      (value "BSS138")
      (footprint "easyedapro:SOT-23-3_L2.9-W1.6-P1.90-LS2.8-BR")
      (fields (field (name "Manufacturer") "TECH PUBLIC(台舟)"))
      (libsource (lib "easyedapro") (part "BSS138_C18212695"))
    )
    (comp (ref "Q7")
      (value "BSS138")
      (footprint "easyedapro:SOT-23-3_L2.9-W1.6-P1.90-LS2.8-BR")
      (fields (field (name "Manufacturer") "TECH PUBLIC(台舟)"))
      (libsource (lib "easyedapro") (part "BSS138_C18212695"))
    )
    (comp (ref "Q8")
      (value "BSS138")
      (footprint "easyedapro:SOT-23-3_L2.9-W1.6-P1.90-LS2.8-BR")
      (fields (field (name "Manufacturer") "TECH PUBLIC(台舟)"))
      (libsource (lib "easyedapro") (part "BSS138_C18212695"))
    )
    (comp (ref "R19")
      (value "10kΩ")
      (footprint "easyedapro:R0603")
      (fields (field (name "Manufacturer Part") "RC0603FR-0710KL") (field (name "Manufacturer") "YAGEO(国巨)"))
      (libsource (lib "easyedapro") (part "RC0603FR-0710KL"))
    )
    (comp (ref "R20")
      (value "10kΩ")
      (footprint "easyedapro:R0603")
      (fields (field (name "Manufacturer Part") "RC0603FR-0710KL") (field (name "Manufacturer") "YAGEO(国巨)"))
      (libsource (lib "easyedapro") (part "RC0603FR-0710KL"))
    )
    (comp (ref "R21")
      (value "10kΩ")
      (footprint "easyedapro:R0603")
      (fields (field (name "Manufacturer Part") "RC0603FR-0710KL") (field (name "Manufacturer") "YAGEO(国巨)"))
      (libsource (lib "easyedapro") (part "RC0603FR-0710KL"))
    )
    (comp (ref "R22")
      (value "10kΩ")
      (footprint "easyedapro:R0603")
      (fields (field (name "Manufacturer Part") "RC0603FR-0710KL") (field (name "Manufacturer") "YAGEO(国巨)"))
      (libsource (lib "easyedapro") (part "RC0603FR-0710KL"))
    )
    (comp (ref "R23")
      (value "10kΩ")
      (footprint "easyedapro:R0603")
      (fields (field (name "Manufacturer Part") "RC0603FR-0710KL") (field (name "Manufacturer") "YAGEO(国巨)"))
      (libsource (lib "easyedapro") (part "RC0603FR-0710KL"))
    )
    (comp (ref "R24")
      (value "10kΩ")
      (footprint "easyedapro:R0603")
      (fields (field (name "Manufacturer Part") "RC0603FR-0710KL") (field (name "Manufacturer") "YAGEO(国巨)"))
      (libsource (lib "easyedapro") (part "RC0603FR-0710KL"))
    )
    (comp (ref "R25")
      (value "10kΩ")
      (footprint "easyedapro:R0603")
      (fields (field (name "Manufacturer Part") "RC0603FR-0710KL") (field (name "Manufacturer") "YAGEO(国巨)"))
      (libsource (lib "easyedapro") (part "RC0603FR-0710KL"))
    )
    (comp (ref "R26")
      (value "10kΩ")
      (footprint "easyedapro:R0603")
      (fields (field (name "Manufacturer Part") "RC0603FR-0710KL") (field (name "Manufacturer") "YAGEO(国巨)"))
      (libsource (lib "easyedapro") (part "RC0603FR-0710KL"))
    )
    (comp (ref "R27")
      (value "10kΩ")
      (footprint "easyedapro:R0603")
      (fields (field (name "Manufacturer Part") "RC0603FR-0710KL") (field (name "Manufacturer") "YAGEO(国巨)"))
      (libsource (lib "easyedapro") (part "RC0603FR-0710KL"))
    )
    (comp (ref "R28")
      (value "10kΩ")
      (footprint "easyedapro:R0603")
      (fields (field (name "Manufacturer Part") "RC0603FR-0710KL") (field (name "Manufacturer") "YAGEO(国巨)"))
      (libsource (lib "easyedapro") (part "RC0603FR-0710KL"))
    )
    (comp (ref "R29")
      (value "10kΩ")
      (footprint "easyedapro:R0603")
      (fields (field (name "Manufacturer Part") "RC0603FR-0710KL") (field (name "Manufacturer") "YAGEO(国巨)"))
      (libsource (lib "easyedapro") (part "RC0603FR-0710KL"))
    )
    (comp (ref "R30")
      (value "10kΩ")
      (footprint "easyedapro:R0603")
      (fields (field (name "Manufacturer Part") "RC0603FR-0710KL") (field (name "Manufacturer") "YAGEO(国巨)"))
      (libsource (lib "easyedapro") (part "RC0603FR-0710KL"))
    )
    (comp (ref "R31")
      (value "10kΩ")
      (footprint "easyedapro:R0603")
      (fields (field (name "Manufacturer Part") "RC0603FR-0710KL") (field (name "Manufacturer") "YAGEO(国巨)"))
      (libsource (lib "easyedapro") (part "RC0603FR-0710KL"))
    )
    (comp (ref "R32")
      (value "10kΩ")
      (footprint "easyedapro:R0603")
      (fields (field (name "Manufacturer Part") "RC0603FR-0710KL") (field (name "Manufacturer") "YAGEO(国巨)"))
      (libsource (lib "easyedapro") (part "RC0603FR-0710KL"))
    )
    (comp (ref "R33")
      (value "10kΩ")
      (footprint "easyedapro:R0603")
      (fields (field (name "Manufacturer Part") "RC0603FR-0710KL") (field (name "Manufacturer") "YAGEO(国巨)"))
      (libsource (lib "easyedapro") (part "RC0603FR-0710KL"))
    )
    (comp (ref "R34")
      (value "10kΩ")
      (footprint "easyedapro:R0603")
      (fields (field (name "Manufacturer Part") "RC0603FR-0710KL") (field (name "Manufacturer") "YAGEO(国巨)"))
      (libsource (lib "easyedapro") (part "RC0603FR-0710KL"))
    )
    (comp (ref "SONAR0")
      (value "ZX-XH2.54-4PZZ")
      (footprint "easyedapro:CONN-TH_4P-P2.50_4PIN")
      (fields (field (name "Manufacturer") "Megastar(兆星)"))
      (libsource (lib "easyedapro") (part "ZX-XH2.54-4PZZ"))
    )
    (comp (ref "SONAR1")
      (value "ZX-XH2.54-4PZZ")
      (footprint "easyedapro:CONN-TH_4P-P2.50_4PIN")
      (fields (field (name "Manufacturer") "Megastar(兆星)"))
      (libsource (lib "easyedapro") (part "ZX-XH2.54-4PZZ"))
    )
    (comp (ref "SONAR2")
      (value "ZX-XH2.54-4PZZ")
      (footprint "easyedapro:CONN-TH_4P-P2.50_4PIN")
      (fields (field (name "Manufacturer") "Megastar(兆星)"))
      (libsource (lib "easyedapro") (part "ZX-XH2.54-4PZZ"))
    )
    (comp (ref "SONAR3")
      (value "ZX-XH2.54-4PZZ")
      (footprint "easyedapro:CONN-TH_4P-P2.50_4PIN")
      (fields (field (name "Manufacturer") "Megastar(兆星)"))
      (libsource (lib "easyedapro") (part "ZX-XH2.54-4PZZ"))
    )
    (comp (ref "CN1")
      (value "ZX-XH2.54-3PZZ")
      (footprint "easyedapro:CONN-TH_3P-P2.54_2501S-3P")
      (fields (field (name "Manufacturer") "Megastar(兆星)"))
      (libsource (lib "easyedapro") (part "ZX-XH2.54-3PZZ"))
    )
    (comp (ref "CN2")
      (value "ZX-XH2.54-3PZZ")
      (footprint "easyedapro:CONN-TH_3P-P2.54_2501S-3P")
      (fields (field (name "Manufacturer") "Megastar(兆星)"))
      (libsource (lib "easyedapro") (part "ZX-XH2.54-3PZZ"))
    )
    (comp (ref "CN3")
      (value "ZX-XH2.54-3PZZ")
      (footprint "easyedapro:CONN-TH_3P-P2.54_2501S-3P")
      (fields (field (name "Manufacturer") "Megastar(兆星)"))
      (libsource (lib "easyedapro") (part "ZX-XH2.54-3PZZ"))
    )
    (comp (ref "CN50")
      (value "ZX-XH2.54-3PZZ")
      (footprint "easyedapro:CONN-TH_3P-P2.54_2501S-3P")
      (fields (field (name "Manufacturer") "Megastar(兆星)"))
      (libsource (lib "easyedapro") (part "ZX-XH2.54-3PZZ"))
    )
    (comp (ref "CN51")
      (value "ZX-XH2.54-3PZZ")
      (footprint "easyedapro:CONN-TH_3P-P2.54_2501S-3P")
      (fields (field (name "Manufacturer") "Megastar(兆星)"))
      (libsource (lib "easyedapro") (part "ZX-XH2.54-3PZZ"))
    )
    (comp (ref "CN52")
      (value "ZX-XH2.54-3PZZ")
      (footprint "easyedapro:CONN-TH_3P-P2.54_2501S-3P")
      (fields (field (name "Manufacturer") "Megastar(兆星)"))
      (libsource (lib "easyedapro") (part "ZX-XH2.54-3PZZ"))
    )
    (comp (ref "CN53")
      (value "ZX-XH2.54-3PZZ")
      (footprint "easyedapro:CONN-TH_3P-P2.54_2501S-3P")
      (fields (field (name "Manufacturer") "Megastar(兆星)"))
      (libsource (lib "easyedapro") (part "ZX-XH2.54-3PZZ"))
    )
    (comp (ref "CN54")
      (value "ZX-XH2.54-3PZZ")
      (footprint "easyedapro:CONN-TH_3P-P2.54_2501S-3P")
      (fields (field (name "Manufacturer") "Megastar(兆星)"))
      (libsource (lib "easyedapro") (part "ZX-XH2.54-3PZZ"))
    )
    (comp (ref "H1")
      (value "PZ254V-11-03P")
      (footprint "easyedapro:HDR-TH_3P-P2.54-V-M")
      (fields (field (name "Manufacturer") "XFCN(兴飞)"))
      (libsource (lib "easyedapro") (part "PZ254V-11-03P_C2937625"))
    )
    (comp (ref "P2")
      (value "WJ127-5.0-2P")
      (footprint "easyedapro:CONN-TH_2P-P5.00_CPC3703CTR")
      (fields (field (name "Manufacturer") "KANGNEX(康奈克斯电气)"))
      (libsource (lib "easyedapro") (part "WJ127-5.0-2P"))
    )
    (comp (ref "Q13")
      (value "BSS138")
      (footprint "easyedapro:SOT-23-3_L2.9-W1.6-P1.90-LS2.8-BR")
      (fields (field (name "Manufacturer") "TECH PUBLIC(台舟)"))
      (libsource (lib "easyedapro") (part "BSS138_C18212695"))
    )
    (comp (ref "Q14")
      (value "BSS138")
      (footprint "easyedapro:SOT-23-3_L2.9-W1.6-P1.90-LS2.8-BR")
      (fields (field (name "Manufacturer") "TECH PUBLIC(台舟)"))
      (libsource (lib "easyedapro") (part "BSS138_C18212695"))
    )
    (comp (ref "Q15")
      (value "BSS138")
      (footprint "easyedapro:SOT-23-3_L2.9-W1.6-P1.90-LS2.8-BR")
      (fields (field (name "Manufacturer") "TECH PUBLIC(台舟)"))
      (libsource (lib "easyedapro") (part "BSS138_C18212695"))
    )
    (comp (ref "Q16")
      (value "BSS138")
      (footprint "easyedapro:SOT-23-3_L2.9-W1.6-P1.90-LS2.8-BR")
      (fields (field (name "Manufacturer") "TECH PUBLIC(台舟)"))
      (libsource (lib "easyedapro") (part "BSS138_C18212695"))
    )
  )
  (nets
    (net (code "1") (name "3.3V") (class "Default")
      (node (ref "CN10") (pin "1") (pinfunction "1_1") (pintype "unspecified"))
      (node (ref "CN11") (pin "1") (pinfunction "1_1") (pintype "unspecified"))
      (node (ref "CN12") (pin "1") (pinfunction "1_1") (pintype "unspecified"))
      (node (ref "CN13") (pin "1") (pinfunction "1_1") (pintype "unspecified"))
      (node (ref "CN14") (pin "1") (pinfunction "1_1") (pintype "unspecified"))
      (node (ref "CN15") (pin "1") (pinfunction "1_1") (pintype "unspecified"))
      (node (ref "CN16") (pin "1") (pinfunction "1_1") (pintype "unspecified"))
      (node (ref "CN17") (pin "1") (pinfunction "1_1") (pintype "unspecified"))
      (node (ref "CN18") (pin "1") (pinfunction "1_1") (pintype "unspecified"))
      (node (ref "CN19") (pin "1") (pinfunction "1_1") (pintype "unspecified"))
      (node (ref "CN20") (pin "1") (pinfunction "1_1") (pintype "unspecified"))
      (node (ref "CN21") (pin "1") (pinfunction "1_1") (pintype "unspecified"))
      (node (ref "CN56") (pin "1") (pinfunction "1_1") (pintype "unspecified"))
      (node (ref "CN57") (pin "1") (pinfunction "1_1") (pintype "unspecified"))
      (node (ref "CN58") (pin "1") (pinfunction "1_1") (pintype "unspecified"))
      (node (ref "CN59") (pin "1") (pinfunction "1_1") (pintype "unspecified"))
      (node (ref "CN60") (pin "1") (pinfunction "1_1") (pintype "unspecified"))
      (node (ref "CN61") (pin "1") (pinfunction "1_1") (pintype "unspecified"))
      (node (ref "CN62") (pin "1") (pinfunction "1_1") (pintype "unspecified"))
      (node (ref "CN63") (pin "1") (pinfunction "1_1") (pintype "unspecified"))
      (node (ref "Q1") (pin "1") (pinfunction "G_1") (pintype "unspecified"))
      (node (ref "Q2") (pin "1") (pinfunction "G_1") (pintype "unspecified"))
      (node (ref "Q3") (pin "1") (pinfunction "G_1") (pintype "unspecified"))
      (node (ref "Q4") (pin "1") (pinfunction "G_1") (pintype "unspecified"))
      (node (ref "Q5") (pin "1") (pinfunction "G_1") (pintype "unspecified"))
      (node (ref "Q6") (pin "1") (pinfunction "G_1") (pintype "unspecified"))
      (node (ref "Q7") (pin "1") (pinfunction "G_1") (pintype "unspecified"))
      (node (ref "Q8") (pin "1") (pinfunction "G_1") (pintype "unspecified"))
      (node (ref "R1") (pin "1") (pinfunction "1_1") (pintype "input"))
      (node (ref "R10") (pin "2") (pinfunction "2_2") (pintype "input"))
      (node (ref "R11") (pin "2") (pinfunction "2_2") (pintype "input"))
      (node (ref "R12") (pin "2") (pinfunction "2_2") (pintype "input"))
      (node (ref "R13") (pin "2") (pinfunction "2_2") (pintype "input"))
      (node (ref "R14") (pin "2") (pinfunction "2_2") (pintype "input"))
      (node (ref "R15") (pin "2") (pinfunction "2_2") (pintype "input"))
      (node (ref "R16") (pin "2") (pinfunction "2_2") (pintype "input"))
      (node (ref "R17") (pin "2") (pinfunction "2_2") (pintype "input"))
      (node (ref "R18") (pin "2") (pinfunction "2_2") (pintype "input"))
      (node (ref "R2") (pin "1") (pinfunction "1_1") (pintype "input"))
      (node (ref "R20") (pin "1") (pinfunction "1_1") (pintype "input"))
      (node (ref "R22") (pin "2") (pinfunction "2_2") (pintype "input"))
      (node (ref "R24") (pin "1") (pinfunction "1_1") (pintype "input"))
      (node (ref "R26") (pin "2") (pinfunction "2_2") (pintype "input"))
      (node (ref "R28") (pin "1") (pinfunction "1_1") (pintype "input"))
      (node (ref "R3") (pin "1") (pinfunction "1_1") (pintype "input"))
      (node (ref "R30") (pin "2") (pinfunction "2_2") (pintype "input"))
      (node (ref "R32") (pin "1") (pinfunction "1_1") (pintype "input"))
      (node (ref "R34") (pin "2") (pinfunction "2_2") (pintype "input"))
      (node (ref "R4") (pin "1") (pinfunction "1_1") (pintype "input"))
      (node (ref "R5") (pin "1") (pinfunction "1_1") (pintype "input"))
      (node (ref "R6") (pin "1") (pinfunction "1_1") (pintype "input"))
      (node (ref "R7") (pin "1") (pinfunction "1_1") (pintype "input"))
      (node (ref "R8") (pin "1") (pinfunction "1_1") (pintype "input"))
      (node (ref "R9") (pin "2") (pinfunction "2_2") (pintype "input"))
      (node (ref "U1") (pin "15") (pinfunction "3.3V_15") (pintype "unspecified"))
      (node (ref "U1") (pin "46") (pinfunction "3.3V_46") (pintype "unspecified"))
      (node (ref "U2") (pin "24") (pinfunction "VCC_24") (pintype "unspecified"))
      (node (ref "U5") (pin "1") (pinfunction "1_1") (pintype "unspecified"))
      (node (ref "U6") (pin "1") (pinfunction "1_1") (pintype "unspecified"))
    )
    (net (code "2") (name "5V") (class "Default")
      (node (ref "CN1") (pin "3") (pinfunction "3_3") (pintype "unspecified"))
      (node (ref "CN2") (pin "3") (pinfunction "3_3") (pintype "unspecified"))
      (node (ref "CN3") (pin "3") (pinfunction "3_3") (pintype "unspecified"))
      (node (ref "CN54") (pin "3") (pinfunction "3_3") (pintype "unspecified"))
      (node (ref "H1") (pin "1") (pinfunction "1_1") (pintype "unspecified"))
      (node (ref "P1") (pin "2") (pinfunction "2_2") (pintype "input"))
      (node (ref "R19") (pin "1") (pinfunction "1_1") (pintype "input"))
      (node (ref "R21") (pin "2") (pinfunction "2_2") (pintype "input"))
      (node (ref "R23") (pin "1") (pinfunction "1_1") (pintype "input"))
      (node (ref "R25") (pin "2") (pinfunction "2_2") (pintype "input"))
      (node (ref "R27") (pin "1") (pinfunction "1_1") (pintype "input"))
      (node (ref "R29") (pin "2") (pinfunction "2_2") (pintype "input"))
      (node (ref "R31") (pin "1") (pinfunction "1_1") (pintype "input"))
      (node (ref "R33") (pin "2") (pinfunction "2_2") (pintype "input"))
      (node (ref "SONAR0") (pin "1") (pinfunction "1_1") (pintype "unspecified"))
      (node (ref "SONAR1") (pin "1") (pinfunction "1_1") (pintype "unspecified"))
      (node (ref "SONAR2") (pin "1") (pinfunction "1_1") (pintype "unspecified"))
      (node (ref "SONAR3") (pin "1") (pinfunction "1_1") (pintype "unspecified"))
      (node (ref "U1") (pin "48") (pinfunction "VIN_48") (pintype "unspecified"))
      (node (ref "U4") (pin "1") (pinfunction "1_1") (pintype "unspecified"))
      (node (ref "U8") (pin "1") (pinfunction "1_1") (pintype "unspecified"))
    )
    (net (code "3") (name "A10") (class "Default")
      (node (ref "CN63") (pin "3") (pinfunction "3_3") (pintype "unspecified"))
      (node (ref "U1") (pin "16") (pinfunction "SCL2/TX6/A10_16") (pintype "unspecified"))
    )
    (net (code "4") (name "A11") (class "Default")
      (node (ref "CN62") (pin "3") (pinfunction "3_3") (pintype "unspecified"))
      (node (ref "U1") (pin "17") (pinfunction "SDA2/RX6/A11_17") (pintype "unspecified"))
    )
    (net (code "5") (name "A12") (class "Default")
      (node (ref "CN61") (pin "3") (pinfunction "3_3") (pintype "unspecified"))
      (node (ref "U1") (pin "18") (pinfunction "MOSI1/A12_18") (pintype "unspecified"))
    )
    (net (code "6") (name "A13") (class "Default")
      (node (ref "CN60") (pin "3") (pinfunction "3_3") (pintype "unspecified"))
      (node (ref "U1") (pin "19") (pinfunction "SCK1/A13_19") (pintype "unspecified"))
    )
    (net (code "7") (name "A14") (class "Default")
      (node (ref "CN59") (pin "3") (pinfunction "3_3") (pintype "unspecified"))
      (node (ref "U1") (pin "30") (pinfunction "INN/CS1/A14_30") (pintype "unspecified"))
    )
    (net (code "8") (name "A15") (class "Default")
      (node (ref "CN58") (pin "3") (pinfunction "3_3") (pintype "unspecified"))
      (node (ref "U1") (pin "31") (pinfunction "OUT1A/MISO1/A15_31") (pintype "unspecified"))
    )
    (net (code "9") (name "A16") (class "Default")
      (node (ref "CN57") (pin "3") (pinfunction "3_3") (pintype "unspecified"))
      (node (ref "U1") (pin "32") (pinfunction "A16_32") (pintype "unspecified"))
    )
    (net (code "10") (name "A17") (class "Default")
      (node (ref "CN56") (pin "3") (pinfunction "3_3") (pintype "unspecified"))
      (node (ref "U1") (pin "33") (pinfunction "A17_33") (pintype "unspecified"))
    )
    (net (code "11") (name "BCLK2") (class "Default")
      (node (ref "CN50") (pin "3") (pinfunction "3_3") (pintype "unspecified"))
      (node (ref "U1") (pin "6") (pinfunction "BCLK2_6") (pintype "unspecified"))
    )
    (net (code "12") (name "CRX1") (class "Default")
      (node (ref "CN10") (pin "3") (pinfunction "3_3") (pintype "unspecified"))
      (node (ref "U1") (pin "45") (pinfunction "CRX1/A9_45") (pintype "unspecified"))
    )
    (net (code "13") (name "CRX3") (class "Default")
      (node (ref "U1") (pin "22") (pinfunction "CRX3_22") (pintype "unspecified"))
      (node (ref "U5") (pin "5") (pinfunction "5_5") (pintype "unspecified"))
    )
    (net (code "14") (name "CS") (class "Default")
      (node (ref "U1") (pin "12") (pinfunction "MQSR/CS_12") (pintype "unspecified"))
      (node (ref "U4") (pin "6") (pinfunction "6_6") (pintype "unspecified"))
    )
    (net (code "15") (name "CTX1") (class "Default")
      (node (ref "CN10") (pin "4") (pinfunction "4_4") (pintype "unspecified"))
      (node (ref "U1") (pin "44") (pinfunction "CTX1/A8_44") (pintype "unspecified"))
    )
    (net (code "16") (name "CTX3") (class "Default")
      (node (ref "U1") (pin "23") (pinfunction "CTX3_23") (pintype "unspecified"))
      (node (ref "U6") (pin "5") (pinfunction "5_5") (pintype "unspecified"))
    )
    (net (code "17") (name "ECHO0") (class "Default")
      (node (ref "Q2") (pin "3") (pinfunction "D_3") (pintype "unspecified"))
      (node (ref "R22") (pin "1") (pinfunction "1_1") (pintype "input"))
      (node (ref "U1") (pin "25") (pinfunction "MCLK2_25") (pintype "unspecified"))
    )
    (net (code "18") (name "ECHO1") (class "Default")
      (node (ref "Q4") (pin "3") (pinfunction "D_3") (pintype "unspecified"))
      (node (ref "R26") (pin "1") (pinfunction "1_1") (pintype "input"))
      (node (ref "U1") (pin "27") (pinfunction "TX8_27") (pintype "unspecified"))
    )
    (net (code "19") (name "ECHO2") (class "Default")
      (node (ref "Q6") (pin "3") (pinfunction "D_3") (pintype "unspecified"))
      (node (ref "R30") (pin "1") (pinfunction "1_1") (pintype "input"))
      (node (ref "U1") (pin "29") (pinfunction "CS_29") (pintype "unspecified"))
    )
    (net (code "20") (name "ECHO3") (class "Default")
      (node (ref "Q8") (pin "3") (pinfunction "D_3") (pintype "unspecified"))
      (node (ref "R34") (pin "1") (pinfunction "1_1") (pintype "input"))
      (node (ref "U1") (pin "37") (pinfunction "RX3/A1_37") (pintype "unspecified"))
    )
    (net (code "21") (name "GND") (class "Default")
      (node (ref "CN1") (pin "2") (pinfunction "2_2") (pintype "unspecified"))
      (node (ref "CN10") (pin "2") (pinfunction "2_2") (pintype "unspecified"))
      (node (ref "CN11") (pin "2") (pinfunction "2_2") (pintype "unspecified"))
      (node (ref "CN12") (pin "2") (pinfunction "2_2") (pintype "unspecified"))
      (node (ref "CN13") (pin "2") (pinfunction "2_2") (pintype "unspecified"))
      (node (ref "CN14") (pin "2") (pinfunction "2_2") (pintype "unspecified"))
      (node (ref "CN15") (pin "2") (pinfunction "2_2") (pintype "unspecified"))
      (node (ref "CN16") (pin "2") (pinfunction "2_2") (pintype "unspecified"))
      (node (ref "CN17") (pin "2") (pinfunction "2_2") (pintype "unspecified"))
      (node (ref "CN18") (pin "2") (pinfunction "2_2") (pintype "unspecified"))
      (node (ref "CN19") (pin "2") (pinfunction "2_2") (pintype "unspecified"))
      (node (ref "CN2") (pin "2") (pinfunction "2_2") (pintype "unspecified"))
      (node (ref "CN20") (pin "2") (pinfunction "2_2") (pintype "unspecified"))
      (node (ref "CN21") (pin "2") (pinfunction "2_2") (pintype "unspecified"))
      (node (ref "CN3") (pin "2") (pinfunction "2_2") (pintype "unspecified"))
      (node (ref "CN50") (pin "2") (pinfunction "2_2") (pintype "unspecified"))
      (node (ref "CN51") (pin "2") (pinfunction "2_2") (pintype "unspecified"))
      (node (ref "CN52") (pin "2") (pinfunction "2_2") (pintype "unspecified"))
      (node (ref "CN53") (pin "2") (pinfunction "2_2") (pintype "unspecified"))
      (node (ref "CN54") (pin "2") (pinfunction "2_2") (pintype "unspecified"))
      (node (ref "CN56") (pin "2") (pinfunction "2_2") (pintype "unspecified"))
      (node (ref "CN57") (pin "2") (pinfunction "2_2") (pintype "unspecified"))
      (node (ref "CN58") (pin "2") (pinfunction "2_2") (pintype "unspecified"))
      (node (ref "CN59") (pin "2") (pinfunction "2_2") (pintype "unspecified"))
      (node (ref "CN60") (pin "2") (pinfunction "2_2") (pintype "unspecified"))
      (node (ref "CN61") (pin "2") (pinfunction "2_2") (pintype "unspecified"))
      (node (ref "CN62") (pin "2") (pinfunction "2_2") (pintype "unspecified"))
      (node (ref "CN63") (pin "2") (pinfunction "2_2") (pintype "unspecified"))
      (node (ref "P1") (pin "1") (pinfunction "1_1") (pintype "input"))
      (node (ref "P2") (pin "1") (pinfunction "1_1") (pintype "input"))
      (node (ref "Q13") (pin "2") (pinfunction "S_2") (pintype "unspecified"))
      (node (ref "Q14") (pin "2") (pinfunction "S_2") (pintype "unspecified"))
      (node (ref "Q15") (pin "2") (pinfunction "S_2") (pintype "unspecified"))
      (node (ref "Q16") (pin "2") (pinfunction "S_2") (pintype "unspecified"))
      (node (ref "SONAR0") (pin "2") (pinfunction "2_2") (pintype "unspecified"))
      (node (ref "SONAR1") (pin "2") (pinfunction "2_2") (pintype "unspecified"))
      (node (ref "SONAR2") (pin "2") (pinfunction "2_2") (pintype "unspecified"))
      (node (ref "SONAR3") (pin "2") (pinfunction "2_2") (pintype "unspecified"))
      (node (ref "U1") (pin "1") (pinfunction "GND_1") (pintype "unspecified"))
      (node (ref "U1") (pin "34") (pinfunction "GND_34") (pintype "unspecified"))
      (node (ref "U1") (pin "47") (pinfunction "GND_47") (pintype "unspecified"))
      (node (ref "U2") (pin "1") (pinfunction "A0_1") (pintype "unspecified"))
      (node (ref "U2") (pin "12") (pinfunction "GND_12") (pintype "unspecified"))
      (node (ref "U2") (pin "2") (pinfunction "A1_2") (pintype "unspecified"))
      (node (ref "U2") (pin "21") (pinfunction "A2_21") (pintype "unspecified"))
      (node (ref "U4") (pin "2") (pinfunction "2_2") (pintype "unspecified"))
      (node (ref "U5") (pin "2") (pinfunction "2_2") (pintype "unspecified"))
      (node (ref "U6") (pin "2") (pinfunction "2_2") (pintype "unspecified"))
      (node (ref "U8") (pin "2") (pinfunction "2_2") (pintype "unspecified"))
    )
    (net (code "22") (name "I2CRESET") (class "Default")
      (node (ref "U1") (pin "10") (pinfunction "IN1/TX2_10") (pintype "unspecified"))
      (node (ref "U2") (pin "3") (pinfunction "RESET#_3") (pintype "unspecified"))
    )
    (net (code "23") (name "IN2") (class "Default")
      (node (ref "CN51") (pin "3") (pinfunction "3_3") (pintype "unspecified"))
      (node (ref "U1") (pin "7") (pinfunction "IN2_7") (pintype "unspecified"))
    )
    (net (code "24") (name "LRCLK2") (class "Default")
      (node (ref "Q16") (pin "1") (pinfunction "G_1") (pintype "unspecified"))
      (node (ref "U1") (pin "5") (pinfunction "LRCLK2_5") (pintype "unspecified"))
    )
    (net (code "25") (name "MISO") (class "Default")
      (node (ref "U1") (pin "14") (pinfunction "MQSL/MISO_14") (pintype "unspecified"))
      (node (ref "U4") (pin "4") (pinfunction "4_4") (pintype "unspecified"))
      (node (ref "U8") (pin "4") (pinfunction "4_4") (pintype "unspecified"))
    )
    (net (code "26") (name "MOSI") (class "Default")
      (node (ref "U1") (pin "13") (pinfunction "CTX1/MOSI_13") (pintype "unspecified"))
      (node (ref "U4") (pin "3") (pinfunction "3_3") (pintype "unspecified"))
      (node (ref "U8") (pin "3") (pinfunction "3_3") (pintype "unspecified"))
    )
    (net (code "27") (name "Net-(CN50-Pad1)") (class "Default")
      (node (ref "CN50") (pin "1") (pinfunction "1_1") (pintype "unspecified"))
      (node (ref "CN51") (pin "1") (pinfunction "1_1") (pintype "unspecified"))
      (node (ref "CN52") (pin "1") (pinfunction "1_1") (pintype "unspecified"))
      (node (ref "CN53") (pin "1") (pinfunction "1_1") (pintype "unspecified"))
      (node (ref "H1") (pin "2") (pinfunction "2_2") (pintype "unspecified"))
    )
    (net (code "28") (name "Net-(H1-Pad3)") (class "Default")
      (node (ref "H1") (pin "3") (pinfunction "3_3") (pintype "unspecified"))
      (node (ref "P2") (pin "2") (pinfunction "2_2") (pintype "input"))
    )
    (net (code "29") (name "Net-(Q1-D)") (class "Default")
      (node (ref "Q1") (pin "3") (pinfunction "D_3") (pintype "unspecified"))
      (node (ref "R19") (pin "2") (pinfunction "2_2") (pintype "input"))
      (node (ref "SONAR0") (pin "3") (pinfunction "3_3") (pintype "unspecified"))
    )
    (net (code "30") (name "Net-(Q2-S)") (class "Default")
      (node (ref "Q2") (pin "2") (pinfunction "S_2") (pintype "unspecified"))
      (node (ref "R21") (pin "1") (pinfunction "1_1") (pintype "input"))
      (node (ref "SONAR0") (pin "4") (pinfunction "4_4") (pintype "unspecified"))
    )
    (net (code "31") (name "Net-(Q3-D)") (class "Default")
      (node (ref "Q3") (pin "3") (pinfunction "D_3") (pintype "unspecified"))
      (node (ref "R23") (pin "2") (pinfunction "2_2") (pintype "input"))
      (node (ref "SONAR1") (pin "3") (pinfunction "3_3") (pintype "unspecified"))
    )
    (net (code "32") (name "Net-(Q4-S)") (class "Default")
      (node (ref "Q4") (pin "2") (pinfunction "S_2") (pintype "unspecified"))
      (node (ref "R25") (pin "1") (pinfunction "1_1") (pintype "input"))
      (node (ref "SONAR1") (pin "4") (pinfunction "4_4") (pintype "unspecified"))
    )
    (net (code "33") (name "Net-(Q5-D)") (class "Default")
      (node (ref "Q5") (pin "3") (pinfunction "D_3") (pintype "unspecified"))
      (node (ref "R27") (pin "2") (pinfunction "2_2") (pintype "input"))
      (node (ref "SONAR2") (pin "3") (pinfunction "3_3") (pintype "unspecified"))
    )
    (net (code "34") (name "Net-(Q6-S)") (class "Default")
      (node (ref "Q6") (pin "2") (pinfunction "S_2") (pintype "unspecified"))
      (node (ref "R29") (pin "1") (pinfunction "1_1") (pintype "input"))
      (node (ref "SONAR2") (pin "4") (pinfunction "4_4") (pintype "unspecified"))
    )
    (net (code "35") (name "Net-(Q7-D)") (class "Default")
      (node (ref "Q7") (pin "3") (pinfunction "D_3") (pintype "unspecified"))
      (node (ref "R31") (pin "2") (pinfunction "2_2") (pintype "input"))
      (node (ref "SONAR3") (pin "3") (pinfunction "3_3") (pintype "unspecified"))
    )
    (net (code "36") (name "Net-(Q8-S)") (class "Default")
      (node (ref "Q8") (pin "2") (pinfunction "S_2") (pintype "unspecified"))
      (node (ref "R33") (pin "1") (pinfunction "1_1") (pintype "input"))
      (node (ref "SONAR3") (pin "4") (pinfunction "4_4") (pintype "unspecified"))
    )
    (net (code "37") (name "Net-(Q13-D)") (class "Default")
      (node (ref "CN3") (pin "1") (pinfunction "1_1") (pintype "unspecified"))
      (node (ref "Q13") (pin "3") (pinfunction "D_3") (pintype "unspecified"))
    )
    (net (code "38") (name "Net-(Q14-D)") (class "Default")
      (node (ref "CN54") (pin "1") (pinfunction "1_1") (pintype "unspecified"))
      (node (ref "Q14") (pin "3") (pinfunction "D_3") (pintype "unspecified"))
    )
    (net (code "39") (name "Net-(Q15-D)") (class "Default")
      (node (ref "CN2") (pin "1") (pinfunction "1_1") (pintype "unspecified"))
      (node (ref "Q15") (pin "3") (pinfunction "D_3") (pintype "unspecified"))
    )
    (net (code "40") (name "Net-(Q16-D)") (class "Default")
      (node (ref "CN1") (pin "1") (pinfunction "1_1") (pintype "unspecified"))
      (node (ref "Q16") (pin "3") (pinfunction "D_3") (pintype "unspecified"))
    )
    (net (code "41") (name "Net-(U2-SC0)") (class "Default")
      (node (ref "CN14") (pin "3") (pinfunction "3_3") (pintype "unspecified"))
      (node (ref "R2") (pin "2") (pinfunction "2_2") (pintype "input"))
      (node (ref "U2") (pin "5") (pinfunction "SC0_5") (pintype "unspecified"))
    )
    (net (code "42") (name "Net-(U2-SC1)") (class "Default")
      (node (ref "CN15") (pin "3") (pinfunction "3_3") (pintype "unspecified"))
      (node (ref "R4") (pin "2") (pinfunction "2_2") (pintype "input"))
      (node (ref "U2") (pin "7") (pinfunction "SC1_7") (pintype "unspecified"))
    )
    (net (code "43") (name "Net-(U2-SC2)") (class "Default")
      (node (ref "CN16") (pin "3") (pinfunction "3_3") (pintype "unspecified"))
      (node (ref "R6") (pin "2") (pinfunction "2_2") (pintype "input"))
      (node (ref "U2") (pin "9") (pinfunction "SC2_9") (pintype "unspecified"))
    )
    (net (code "44") (name "Net-(U2-SC3)") (class "Default")
      (node (ref "CN17") (pin "3") (pinfunction "3_3") (pintype "unspecified"))
      (node (ref "R8") (pin "2") (pinfunction "2_2") (pintype "input"))
      (node (ref "U2") (pin "11") (pinfunction "SC3_11") (pintype "unspecified"))
    )
    (net (code "45") (name "Net-(U2-SC4)") (class "Default")
      (node (ref "CN18") (pin "3") (pinfunction "3_3") (pintype "unspecified"))
      (node (ref "R15") (pin "1") (pinfunction "1_1") (pintype "input"))
      (node (ref "U2") (pin "14") (pinfunction "SC4_14") (pintype "unspecified"))
    )
    (net (code "46") (name "Net-(U2-SC5)") (class "Default")
      (node (ref "CN19") (pin "3") (pinfunction "3_3") (pintype "unspecified"))
      (node (ref "R13") (pin "1") (pinfunction "1_1") (pintype "input"))
      (node (ref "U2") (pin "16") (pinfunction "SC5_16") (pintype "unspecified"))
    )
    (net (code "47") (name "Net-(U2-SC6)") (class "Default")
      (node (ref "CN20") (pin "3") (pinfunction "3_3") (pintype "unspecified"))
      (node (ref "R11") (pin "1") (pinfunction "1_1") (pintype "input"))
      (node (ref "U2") (pin "18") (pinfunction "SC6_18") (pintype "unspecified"))
    )
    (net (code "48") (name "Net-(U2-SC7)") (class "Default")
      (node (ref "CN21") (pin "3") (pinfunction "3_3") (pintype "unspecified"))
      (node (ref "R9") (pin "1") (pinfunction "1_1") (pintype "input"))
      (node (ref "U2") (pin "20") (pinfunction "SC7_20") (pintype "unspecified"))
    )
    (net (code "49") (name "Net-(U2-SD0)") (class "Default")
      (node (ref "CN14") (pin "4") (pinfunction "4_4") (pintype "unspecified"))
      (node (ref "R1") (pin "2") (pinfunction "2_2") (pintype "input"))
      (node (ref "U2") (pin "4") (pinfunction "SD0_4") (pintype "unspecified"))
    )
    (net (code "50") (name "Net-(U2-SD1)") (class "Default")
      (node (ref "CN15") (pin "4") (pinfunction "4_4") (pintype "unspecified"))
      (node (ref "R3") (pin "2") (pinfunction "2_2") (pintype "input"))
      (node (ref "U2") (pin "6") (pinfunction "SD1_6") (pintype "unspecified"))
    )
    (net (code "51") (name "Net-(U2-SD2)") (class "Default")
      (node (ref "CN16") (pin "4") (pinfunction "4_4") (pintype "unspecified"))
      (node (ref "R5") (pin "2") (pinfunction "2_2") (pintype "input"))
      (node (ref "U2") (pin "8") (pinfunction "SD2_8") (pintype "unspecified"))
    )
    (net (code "52") (name "Net-(U2-SD3)") (class "Default")
      (node (ref "CN17") (pin "4") (pinfunction "4_4") (pintype "unspecified"))
      (node (ref "R7") (pin "2") (pinfunction "2_2") (pintype "input"))
      (node (ref "U2") (pin "10") (pinfunction "SD3_10") (pintype "unspecified"))
    )
    (net (code "53") (name "Net-(U2-SD4)") (class "Default")
      (node (ref "CN18") (pin "4") (pinfunction "4_4") (pintype "unspecified"))
      (node (ref "R16") (pin "1") (pinfunction "1_1") (pintype "input"))
      (node (ref "U2") (pin "13") (pinfunction "SD4_13") (pintype "unspecified"))
    )
    (net (code "54") (name "Net-(U2-SD5)") (class "Default")
      (node (ref "CN19") (pin "4") (pinfunction "4_4") (pintype "unspecified"))
      (node (ref "R14") (pin "1") (pinfunction "1_1") (pintype "input"))
      (node (ref "U2") (pin "15") (pinfunction "SD5_15") (pintype "unspecified"))
    )
    (net (code "55") (name "Net-(U2-SD6)") (class "Default")
      (node (ref "CN20") (pin "4") (pinfunction "4_4") (pintype "unspecified"))
      (node (ref "R12") (pin "1") (pinfunction "1_1") (pintype "input"))
      (node (ref "U2") (pin "17") (pinfunction "SD6_17") (pintype "unspecified"))
    )
    (net (code "56") (name "Net-(U2-SD7)") (class "Default")
      (node (ref "CN21") (pin "4") (pinfunction "4_4") (pintype "unspecified"))
      (node (ref "R10") (pin "1") (pinfunction "1_1") (pintype "input"))
      (node (ref "U2") (pin "19") (pinfunction "SD7_19") (pintype "unspecified"))
    )
    (net (code "57") (name "OUT1A") (class "Default")
      (node (ref "CN53") (pin "3") (pinfunction "3_3") (pintype "unspecified"))
      (node (ref "U1") (pin "9") (pinfunction "OUT1A/RX2_9") (pintype "unspecified"))
    )
    (net (code "58") (name "OUT1C") (class "Default")
      (node (ref "U1") (pin "11") (pinfunction "OUT1C_11") (pintype "unspecified"))
      (node (ref "U8") (pin "6") (pinfunction "6_6") (pintype "unspecified"))
    )
    (net (code "59") (name "OUT1D") (class "Default")
      (node (ref "CN52") (pin "3") (pinfunction "3_3") (pintype "unspecified"))
      (node (ref "U1") (pin "8") (pinfunction "OUT1D_8") (pintype "unspecified"))
    )
    (net (code "60") (name "OUT2") (class "Default")
      (node (ref "Q15") (pin "1") (pinfunction "G_1") (pintype "unspecified"))
      (node (ref "U1") (pin "4") (pinfunction "OUT2_4") (pintype "unspecified"))
    )
    (net (code "61") (name "RX1") (class "Default")
      (node (ref "Q13") (pin "1") (pinfunction "G_1") (pintype "unspecified"))
      (node (ref "U1") (pin "2") (pinfunction "CRX2/CS1/RX1_2") (pintype "unspecified"))
    )
    (net (code "62") (name "RX4") (class "Default")
      (node (ref "U1") (pin "38") (pinfunction "RX4/A2_38") (pintype "unspecified"))
      (node (ref "U6") (pin "3") (pinfunction "3_3") (pintype "unspecified"))
    )
    (net (code "63") (name "RX5") (class "Default")
      (node (ref "CN13") (pin "3") (pinfunction "3_3") (pintype "unspecified"))
      (node (ref "U1") (pin "43") (pinfunction "RX5/A7_43") (pintype "unspecified"))
    )
    (net (code "64") (name "RX7") (class "Default")
      (node (ref "U1") (pin "20") (pinfunction "RX7_20") (pintype "unspecified"))
      (node (ref "U5") (pin "3") (pinfunction "3_3") (pintype "unspecified"))
    )
    (net (code "65") (name "SCK") (class "Default")
      (node (ref "U1") (pin "35") (pinfunction "SCK_35") (pintype "unspecified"))
      (node (ref "U4") (pin "5") (pinfunction "5_5") (pintype "unspecified"))
      (node (ref "U8") (pin "5") (pinfunction "5_5") (pintype "unspecified"))
    )
    (net (code "66") (name "SCL") (class "Default")
      (node (ref "CN11") (pin "3") (pinfunction "3_3") (pintype "unspecified"))
      (node (ref "CN12") (pin "3") (pinfunction "3_3") (pintype "unspecified"))
      (node (ref "R17") (pin "1") (pinfunction "1_1") (pintype "input"))
      (node (ref "U1") (pin "41") (pinfunction "A5_41") (pintype "unspecified"))
      (node (ref "U2") (pin "22") (pinfunction "SCL_22") (pintype "unspecified"))
    )
    (net (code "67") (name "SDA") (class "Default")
      (node (ref "CN11") (pin "4") (pinfunction "4_4") (pintype "unspecified"))
      (node (ref "CN12") (pin "4") (pinfunction "4_4") (pintype "unspecified"))
      (node (ref "R18") (pin "1") (pinfunction "1_1") (pintype "input"))
      (node (ref "U1") (pin "40") (pinfunction "A4_40") (pintype "unspecified"))
      (node (ref "U2") (pin "23") (pinfunction "SDA_23") (pintype "unspecified"))
    )
    (net (code "68") (name "TRIG0") (class "Default")
      (node (ref "Q1") (pin "2") (pinfunction "S_2") (pintype "unspecified"))
      (node (ref "R20") (pin "2") (pinfunction "2_2") (pintype "input"))
      (node (ref "U1") (pin "24") (pinfunction "OUT1B_24") (pintype "unspecified"))
    )
    (net (code "69") (name "TRIG1") (class "Default")
      (node (ref "Q3") (pin "2") (pinfunction "S_2") (pintype "unspecified"))
      (node (ref "R24") (pin "2") (pinfunction "2_2") (pintype "input"))
      (node (ref "U1") (pin "26") (pinfunction "RX8_26") (pintype "unspecified"))
    )
    (net (code "70") (name "TRIG2") (class "Default")
      (node (ref "Q5") (pin "2") (pinfunction "S_2") (pintype "unspecified"))
      (node (ref "R28") (pin "2") (pinfunction "2_2") (pintype "input"))
      (node (ref "U1") (pin "28") (pinfunction "CS_28") (pintype "unspecified"))
    )
    (net (code "71") (name "TRIG3") (class "Default")
      (node (ref "Q7") (pin "2") (pinfunction "S_2") (pintype "unspecified"))
      (node (ref "R32") (pin "2") (pinfunction "2_2") (pintype "input"))
      (node (ref "U1") (pin "36") (pinfunction "TX3/A0_36") (pintype "unspecified"))
    )
    (net (code "72") (name "TX1") (class "Default")
      (node (ref "Q14") (pin "1") (pinfunction "G_1") (pintype "unspecified"))
      (node (ref "U1") (pin "3") (pinfunction "CTX2/MISO1/TX1_3") (pintype "unspecified"))
    )
    (net (code "73") (name "TX4") (class "Default")
      (node (ref "U1") (pin "39") (pinfunction "TX4/A3_39") (pintype "unspecified"))
      (node (ref "U6") (pin "4") (pinfunction "4_4") (pintype "unspecified"))
    )
    (net (code "74") (name "TX5") (class "Default")
      (node (ref "CN13") (pin "4") (pinfunction "4_4") (pintype "unspecified"))
      (node (ref "U1") (pin "42") (pinfunction "TX5/A6_42") (pintype "unspecified"))
    )
    (net (code "75") (name "TX7") (class "Default")
      (node (ref "U1") (pin "21") (pinfunction "TX7_21") (pintype "unspecified"))
      (node (ref "U5") (pin "4") (pinfunction "4_4") (pintype "unspecified"))
    )
  )
)
